# Top.net
KiCad netlist of a schematic drawn in Altium Designer
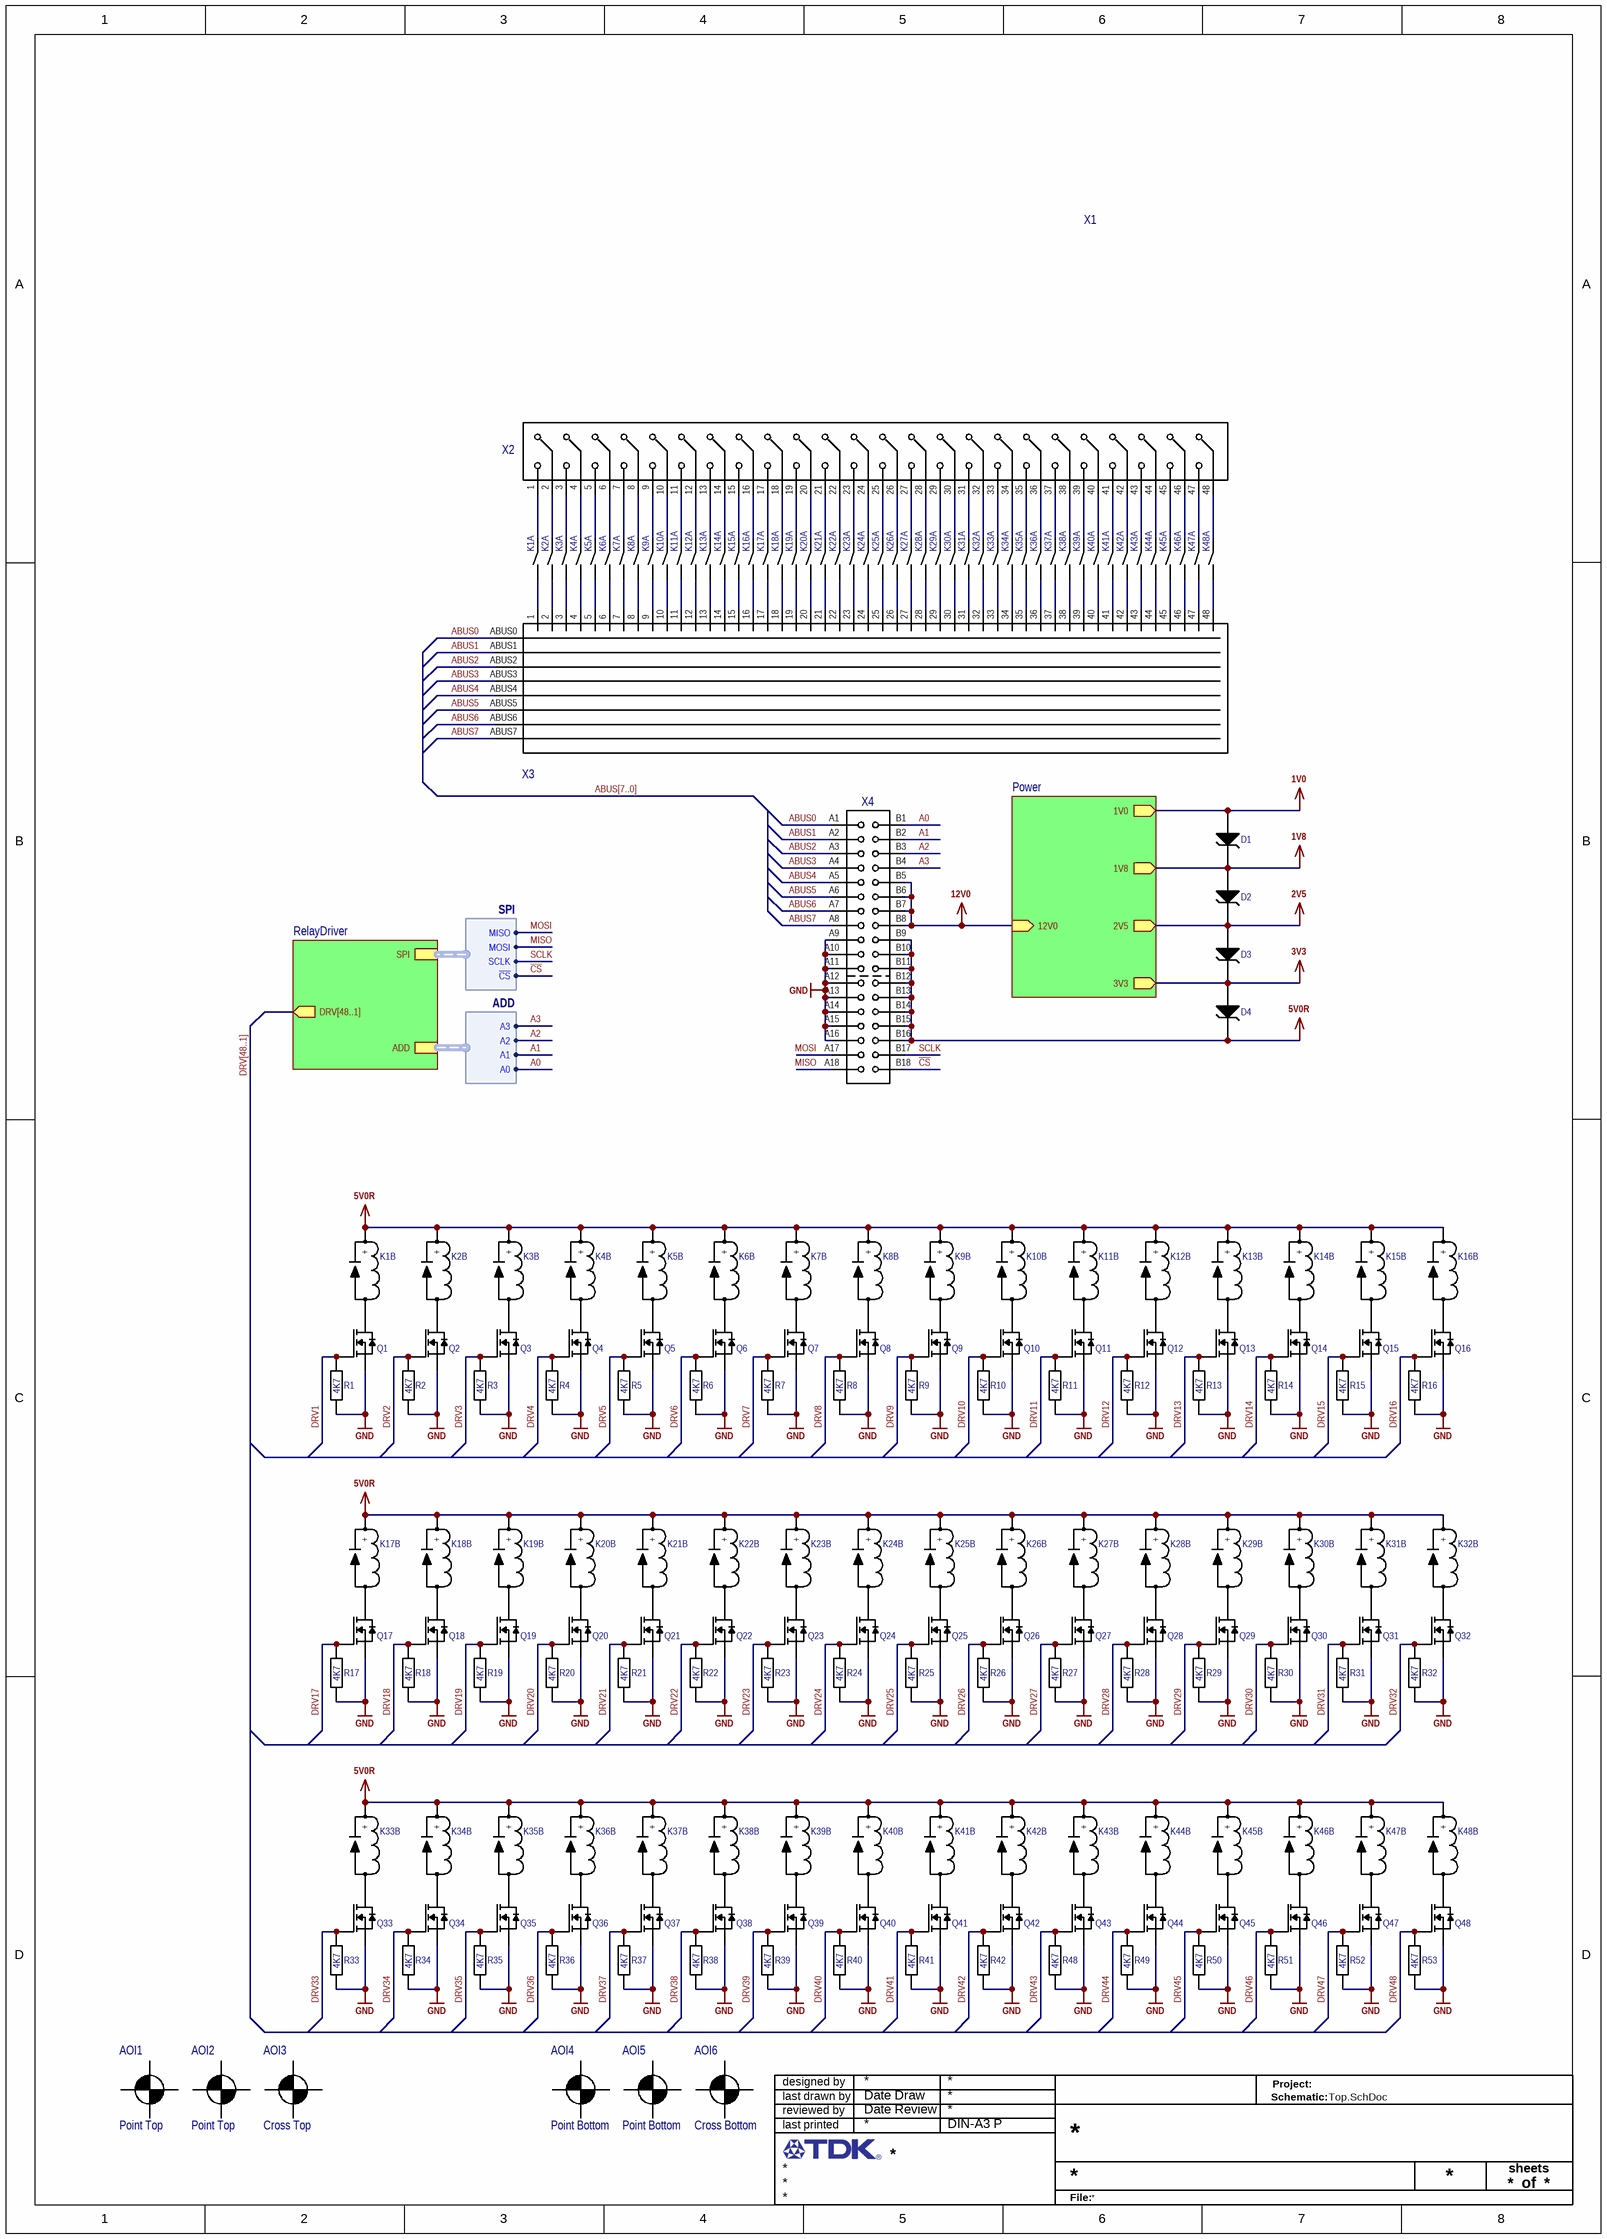
[diagram p0: Top.SchDoc]

(export (version "E")
  (design (tool "Eeschema 10.0.6"))
  (components
    (comp (ref "AOI1")
      (value "AOI")
      (footprint "Fiducial Point")
      (description "Assembly AOI")
      (fields (field (name "SHAPE") "Point Top") (field (name "13. CREATED DATE/NAME") "AUG2018/Hören"))
      (libsource (lib "chickenfood") (part "Fiducial"))
    )
    (comp (ref "AOI2")
      (value "AOI")
      (footprint "Fiducial Point")
      (description "Assembly AOI")
      (fields (field (name "SHAPE") "Point Top") (field (name "13. CREATED DATE/NAME") "AUG2018/Hören"))
      (libsource (lib "chickenfood") (part "Fiducial"))
    )
    (comp (ref "AOI3")
      (value "AOI")
      (footprint "Fiducial Cross")
      (description "Assembly AOI")
      (fields (field (name "SHAPE") "Cross Top") (field (name "13. CREATED DATE/NAME") "AUG2018/Hören"))
      (libsource (lib "chickenfood") (part "Fiducial"))
    )
    (comp (ref "AOI4")
      (value "AOI")
      (footprint "Fiducial Point")
      (description "Assembly AOI")
      (fields (field (name "SHAPE") "Point Bottom") (field (name "13. CREATED DATE/NAME") "AUG2018/Hören"))
      (libsource (lib "chickenfood") (part "Fiducial"))
    )
    (comp (ref "AOI5")
      (value "AOI")
      (footprint "Fiducial Point")
      (description "Assembly AOI")
      (fields (field (name "SHAPE") "Point Bottom") (field (name "13. CREATED DATE/NAME") "AUG2018/Hören"))
      (libsource (lib "chickenfood") (part "Fiducial"))
    )
    (comp (ref "AOI6")
      (value "AOI")
      (footprint "Fiducial Cross")
      (description "Assembly AOI")
      (fields (field (name "SHAPE") "Cross Bottom") (field (name "13. CREATED DATE/NAME") "AUG2018/Hören"))
      (libsource (lib "chickenfood") (part "Fiducial"))
    )
    (comp (ref "D1")
      (value "D")
      (footprint "SOD128")
      (description "DIODE SCHOTTKY 40V 5A SOD128")
      (fields
        (field (name "02. DISTRIBUTOR PART NUMBER") "1727-5842-6-ND")
        (field (name "07. MANUFACTURER  PART NUMBER") "PMEG4050EP,115")
        (field (name "13. CREATED DATE/NAME") "AUG2018/Hören")
      )
      (libsource (lib "chickenfood") (part "Dz"))
    )
    (comp (ref "D2")
      (value "D")
      (footprint "SOD128")
      (description "DIODE SCHOTTKY 40V 5A SOD128")
      (fields
        (field (name "02. DISTRIBUTOR PART NUMBER") "1727-5842-6-ND")
        (field (name "07. MANUFACTURER  PART NUMBER") "PMEG4050EP,115")
        (field (name "13. CREATED DATE/NAME") "AUG2018/Hören")
      )
      (libsource (lib "chickenfood") (part "Dz"))
    )
    (comp (ref "D3")
      (value "D")
      (footprint "SOD128")
      (description "DIODE SCHOTTKY 40V 5A SOD128")
      (fields
        (field (name "02. DISTRIBUTOR PART NUMBER") "1727-5842-6-ND")
        (field (name "07. MANUFACTURER  PART NUMBER") "PMEG4050EP,115")
        (field (name "13. CREATED DATE/NAME") "AUG2018/Hören")
      )
      (libsource (lib "chickenfood") (part "Dz"))
    )
    (comp (ref "D4")
      (value "D")
      (footprint "SOD128")
      (description "DIODE SCHOTTKY 40V 5A SOD128")
      (fields
        (field (name "02. DISTRIBUTOR PART NUMBER") "1727-5842-6-ND")
        (field (name "07. MANUFACTURER  PART NUMBER") "PMEG4050EP,115")
        (field (name "13. CREATED DATE/NAME") "AUG2018/Hören")
      )
      (libsource (lib "chickenfood") (part "Dz"))
    )
    (comp (ref "K1")
      (value "K")
      (footprint "118-1A")
      (description "5V Signal Relais, Normal Open")
      (fields
        (field (name "02. DISTRIBUTOR PART NUMBER") "118-1-A-5/2D")
        (field (name "13. CREATED DATE/NAME") "20.12.17 S. Kaiser")
      )
      (libsource (lib "") (part "118-1-A-5/2D_1"))
    )
    (comp (ref "K2")
      (value "K")
      (footprint "118-1A")
      (description "5V Signal Relais, Normal Open")
      (fields
        (field (name "02. DISTRIBUTOR PART NUMBER") "118-1-A-5/2D")
        (field (name "13. CREATED DATE/NAME") "20.12.17 S. Kaiser")
      )
      (libsource (lib "") (part "118-1-A-5/2D_1"))
    )
    (comp (ref "K3")
      (value "K")
      (footprint "118-1A")
      (description "5V Signal Relais, Normal Open")
      (fields
        (field (name "02. DISTRIBUTOR PART NUMBER") "118-1-A-5/2D")
        (field (name "13. CREATED DATE/NAME") "20.12.17 S. Kaiser")
      )
      (libsource (lib "") (part "118-1-A-5/2D_1"))
    )
    (comp (ref "K4")
      (value "K")
      (footprint "118-1A")
      (description "5V Signal Relais, Normal Open")
      (fields
        (field (name "02. DISTRIBUTOR PART NUMBER") "118-1-A-5/2D")
        (field (name "13. CREATED DATE/NAME") "20.12.17 S. Kaiser")
      )
      (libsource (lib "") (part "118-1-A-5/2D_1"))
    )
    (comp (ref "K5")
      (value "K")
      (footprint "118-1A")
      (description "5V Signal Relais, Normal Open")
      (fields
        (field (name "02. DISTRIBUTOR PART NUMBER") "118-1-A-5/2D")
        (field (name "13. CREATED DATE/NAME") "20.12.17 S. Kaiser")
      )
      (libsource (lib "chickenfood") (part "118-1-A-5/2D"))
    )
    (comp (ref "K6")
      (value "K")
      (footprint "118-1A")
      (description "5V Signal Relais, Normal Open")
      (fields
        (field (name "02. DISTRIBUTOR PART NUMBER") "118-1-A-5/2D")
        (field (name "13. CREATED DATE/NAME") "20.12.17 S. Kaiser")
      )
      (libsource (lib "") (part "118-1-A-5/2D_1"))
    )
    (comp (ref "K7")
      (value "K")
      (footprint "118-1A")
      (description "5V Signal Relais, Normal Open")
      (fields
        (field (name "02. DISTRIBUTOR PART NUMBER") "118-1-A-5/2D")
        (field (name "13. CREATED DATE/NAME") "20.12.17 S. Kaiser")
      )
      (libsource (lib "") (part "118-1-A-5/2D_1"))
    )
    (comp (ref "K8")
      (value "K")
      (footprint "118-1A")
      (description "5V Signal Relais, Normal Open")
      (fields
        (field (name "02. DISTRIBUTOR PART NUMBER") "118-1-A-5/2D")
        (field (name "13. CREATED DATE/NAME") "20.12.17 S. Kaiser")
      )
      (libsource (lib "chickenfood") (part "118-1-A-5/2D"))
    )
    (comp (ref "K9")
      (value "K")
      (footprint "118-1A")
      (description "5V Signal Relais, Normal Open")
      (fields
        (field (name "02. DISTRIBUTOR PART NUMBER") "118-1-A-5/2D")
        (field (name "13. CREATED DATE/NAME") "20.12.17 S. Kaiser")
      )
      (libsource (lib "") (part "118-1-A-5/2D_1"))
    )
    (comp (ref "K10")
      (value "K")
      (footprint "118-1A")
      (description "5V Signal Relais, Normal Open")
      (fields
        (field (name "02. DISTRIBUTOR PART NUMBER") "118-1-A-5/2D")
        (field (name "13. CREATED DATE/NAME") "20.12.17 S. Kaiser")
      )
      (libsource (lib "chickenfood") (part "118-1-A-5/2D"))
    )
    (comp (ref "K11")
      (value "K")
      (footprint "118-1A")
      (description "5V Signal Relais, Normal Open")
      (fields
        (field (name "02. DISTRIBUTOR PART NUMBER") "118-1-A-5/2D")
        (field (name "13. CREATED DATE/NAME") "20.12.17 S. Kaiser")
      )
      (libsource (lib "") (part "118-1-A-5/2D_1"))
    )
    (comp (ref "K12")
      (value "K")
      (footprint "118-1A")
      (description "5V Signal Relais, Normal Open")
      (fields
        (field (name "02. DISTRIBUTOR PART NUMBER") "118-1-A-5/2D")
        (field (name "13. CREATED DATE/NAME") "20.12.17 S. Kaiser")
      )
      (libsource (lib "chickenfood") (part "118-1-A-5/2D"))
    )
    (comp (ref "K13")
      (value "K")
      (footprint "118-1A")
      (description "5V Signal Relais, Normal Open")
      (fields
        (field (name "02. DISTRIBUTOR PART NUMBER") "118-1-A-5/2D")
        (field (name "13. CREATED DATE/NAME") "20.12.17 S. Kaiser")
      )
      (libsource (lib "chickenfood") (part "118-1-A-5/2D"))
    )
    (comp (ref "K14")
      (value "K")
      (footprint "118-1A")
      (description "5V Signal Relais, Normal Open")
      (fields
        (field (name "02. DISTRIBUTOR PART NUMBER") "118-1-A-5/2D")
        (field (name "13. CREATED DATE/NAME") "20.12.17 S. Kaiser")
      )
      (libsource (lib "chickenfood") (part "118-1-A-5/2D"))
    )
    (comp (ref "K15")
      (value "K")
      (footprint "118-1A")
      (description "5V Signal Relais, Normal Open")
      (fields
        (field (name "02. DISTRIBUTOR PART NUMBER") "118-1-A-5/2D")
        (field (name "13. CREATED DATE/NAME") "20.12.17 S. Kaiser")
      )
      (libsource (lib "") (part "118-1-A-5/2D_1"))
    )
    (comp (ref "K16")
      (value "K")
      (footprint "118-1A")
      (description "5V Signal Relais, Normal Open")
      (fields
        (field (name "02. DISTRIBUTOR PART NUMBER") "118-1-A-5/2D")
        (field (name "13. CREATED DATE/NAME") "20.12.17 S. Kaiser")
      )
      (libsource (lib "chickenfood") (part "118-1-A-5/2D"))
    )
    (comp (ref "K17")
      (value "K")
      (footprint "118-1A")
      (description "5V Signal Relais, Normal Open")
      (fields
        (field (name "02. DISTRIBUTOR PART NUMBER") "118-1-A-5/2D")
        (field (name "13. CREATED DATE/NAME") "20.12.17 S. Kaiser")
      )
      (libsource (lib "chickenfood") (part "118-1-A-5/2D"))
    )
    (comp (ref "K18")
      (value "K")
      (footprint "118-1A")
      (description "5V Signal Relais, Normal Open")
      (fields
        (field (name "02. DISTRIBUTOR PART NUMBER") "118-1-A-5/2D")
        (field (name "13. CREATED DATE/NAME") "20.12.17 S. Kaiser")
      )
      (libsource (lib "chickenfood") (part "118-1-A-5/2D"))
    )
    (comp (ref "K19")
      (value "K")
      (footprint "118-1A")
      (description "5V Signal Relais, Normal Open")
      (fields
        (field (name "02. DISTRIBUTOR PART NUMBER") "118-1-A-5/2D")
        (field (name "13. CREATED DATE/NAME") "20.12.17 S. Kaiser")
      )
      (libsource (lib "chickenfood") (part "118-1-A-5/2D"))
    )
    (comp (ref "K20")
      (value "K")
      (footprint "118-1A")
      (description "5V Signal Relais, Normal Open")
      (fields
        (field (name "02. DISTRIBUTOR PART NUMBER") "118-1-A-5/2D")
        (field (name "13. CREATED DATE/NAME") "20.12.17 S. Kaiser")
      )
      (libsource (lib "chickenfood") (part "118-1-A-5/2D"))
    )
    (comp (ref "K21")
      (value "K")
      (footprint "118-1A")
      (description "5V Signal Relais, Normal Open")
      (fields
        (field (name "02. DISTRIBUTOR PART NUMBER") "118-1-A-5/2D")
        (field (name "13. CREATED DATE/NAME") "20.12.17 S. Kaiser")
      )
      (libsource (lib "") (part "118-1-A-5/2D_1"))
    )
    (comp (ref "K22")
      (value "K")
      (footprint "118-1A")
      (description "5V Signal Relais, Normal Open")
      (fields
        (field (name "02. DISTRIBUTOR PART NUMBER") "118-1-A-5/2D")
        (field (name "13. CREATED DATE/NAME") "20.12.17 S. Kaiser")
      )
      (libsource (lib "chickenfood") (part "118-1-A-5/2D"))
    )
    (comp (ref "K23")
      (value "K")
      (footprint "118-1A")
      (description "5V Signal Relais, Normal Open")
      (fields
        (field (name "02. DISTRIBUTOR PART NUMBER") "118-1-A-5/2D")
        (field (name "13. CREATED DATE/NAME") "20.12.17 S. Kaiser")
      )
      (libsource (lib "chickenfood") (part "118-1-A-5/2D"))
    )
    (comp (ref "K24")
      (value "K")
      (footprint "118-1A")
      (description "5V Signal Relais, Normal Open")
      (fields
        (field (name "02. DISTRIBUTOR PART NUMBER") "118-1-A-5/2D")
        (field (name "13. CREATED DATE/NAME") "20.12.17 S. Kaiser")
      )
      (libsource (lib "") (part "118-1-A-5/2D_1"))
    )
    (comp (ref "K25")
      (value "K")
      (footprint "118-1A")
      (description "5V Signal Relais, Normal Open")
      (fields
        (field (name "02. DISTRIBUTOR PART NUMBER") "118-1-A-5/2D")
        (field (name "13. CREATED DATE/NAME") "20.12.17 S. Kaiser")
      )
      (libsource (lib "chickenfood") (part "118-1-A-5/2D"))
    )
    (comp (ref "K26")
      (value "K")
      (footprint "118-1A")
      (description "5V Signal Relais, Normal Open")
      (fields
        (field (name "02. DISTRIBUTOR PART NUMBER") "118-1-A-5/2D")
        (field (name "13. CREATED DATE/NAME") "20.12.17 S. Kaiser")
      )
      (libsource (lib "") (part "118-1-A-5/2D_1"))
    )
    (comp (ref "K27")
      (value "K")
      (footprint "118-1A")
      (description "5V Signal Relais, Normal Open")
      (fields
        (field (name "02. DISTRIBUTOR PART NUMBER") "118-1-A-5/2D")
        (field (name "13. CREATED DATE/NAME") "20.12.17 S. Kaiser")
      )
      (libsource (lib "") (part "118-1-A-5/2D_1"))
    )
    (comp (ref "K28")
      (value "K")
      (footprint "118-1A")
      (description "5V Signal Relais, Normal Open")
      (fields
        (field (name "02. DISTRIBUTOR PART NUMBER") "118-1-A-5/2D")
        (field (name "13. CREATED DATE/NAME") "20.12.17 S. Kaiser")
      )
      (libsource (lib "") (part "118-1-A-5/2D_1"))
    )
    (comp (ref "K29")
      (value "K")
      (footprint "118-1A")
      (description "5V Signal Relais, Normal Open")
      (fields
        (field (name "02. DISTRIBUTOR PART NUMBER") "118-1-A-5/2D")
        (field (name "13. CREATED DATE/NAME") "20.12.17 S. Kaiser")
      )
      (libsource (lib "") (part "118-1-A-5/2D_1"))
    )
    (comp (ref "K30")
      (value "K")
      (footprint "118-1A")
      (description "5V Signal Relais, Normal Open")
      (fields
        (field (name "02. DISTRIBUTOR PART NUMBER") "118-1-A-5/2D")
        (field (name "13. CREATED DATE/NAME") "20.12.17 S. Kaiser")
      )
      (libsource (lib "") (part "118-1-A-5/2D_1"))
    )
    (comp (ref "K31")
      (value "K")
      (footprint "118-1A")
      (description "5V Signal Relais, Normal Open")
      (fields
        (field (name "02. DISTRIBUTOR PART NUMBER") "118-1-A-5/2D")
        (field (name "13. CREATED DATE/NAME") "20.12.17 S. Kaiser")
      )
      (libsource (lib "") (part "118-1-A-5/2D_1"))
    )
    (comp (ref "K32")
      (value "K")
      (footprint "118-1A")
      (description "5V Signal Relais, Normal Open")
      (fields
        (field (name "02. DISTRIBUTOR PART NUMBER") "118-1-A-5/2D")
        (field (name "13. CREATED DATE/NAME") "20.12.17 S. Kaiser")
      )
      (libsource (lib "chickenfood") (part "118-1-A-5/2D"))
    )
    (comp (ref "K33")
      (value "K")
      (footprint "118-1A")
      (description "5V Signal Relais, Normal Open")
      (fields
        (field (name "02. DISTRIBUTOR PART NUMBER") "118-1-A-5/2D")
        (field (name "13. CREATED DATE/NAME") "20.12.17 S. Kaiser")
      )
      (libsource (lib "") (part "118-1-A-5/2D_1"))
    )
    (comp (ref "K34")
      (value "K")
      (footprint "118-1A")
      (description "5V Signal Relais, Normal Open")
      (fields
        (field (name "02. DISTRIBUTOR PART NUMBER") "118-1-A-5/2D")
        (field (name "13. CREATED DATE/NAME") "20.12.17 S. Kaiser")
      )
      (libsource (lib "chickenfood") (part "118-1-A-5/2D"))
    )
    (comp (ref "K35")
      (value "K")
      (footprint "118-1A")
      (description "5V Signal Relais, Normal Open")
      (fields
        (field (name "02. DISTRIBUTOR PART NUMBER") "118-1-A-5/2D")
        (field (name "13. CREATED DATE/NAME") "20.12.17 S. Kaiser")
      )
      (libsource (lib "chickenfood") (part "118-1-A-5/2D"))
    )
    (comp (ref "K36")
      (value "K")
      (footprint "118-1A")
      (description "5V Signal Relais, Normal Open")
      (fields
        (field (name "02. DISTRIBUTOR PART NUMBER") "118-1-A-5/2D")
        (field (name "13. CREATED DATE/NAME") "20.12.17 S. Kaiser")
      )
      (libsource (lib "") (part "118-1-A-5/2D_1"))
    )
    (comp (ref "K37")
      (value "K")
      (footprint "118-1A")
      (description "5V Signal Relais, Normal Open")
      (fields
        (field (name "02. DISTRIBUTOR PART NUMBER") "118-1-A-5/2D")
        (field (name "13. CREATED DATE/NAME") "20.12.17 S. Kaiser")
      )
      (libsource (lib "") (part "118-1-A-5/2D_1"))
    )
    (comp (ref "K38")
      (value "K")
      (footprint "118-1A")
      (description "5V Signal Relais, Normal Open")
      (fields
        (field (name "02. DISTRIBUTOR PART NUMBER") "118-1-A-5/2D")
        (field (name "13. CREATED DATE/NAME") "20.12.17 S. Kaiser")
      )
      (libsource (lib "chickenfood") (part "118-1-A-5/2D"))
    )
    (comp (ref "K39")
      (value "K")
      (footprint "118-1A")
      (description "5V Signal Relais, Normal Open")
      (fields
        (field (name "02. DISTRIBUTOR PART NUMBER") "118-1-A-5/2D")
        (field (name "13. CREATED DATE/NAME") "20.12.17 S. Kaiser")
      )
      (libsource (lib "") (part "118-1-A-5/2D_1"))
    )
    (comp (ref "K40")
      (value "K")
      (footprint "118-1A")
      (description "5V Signal Relais, Normal Open")
      (fields
        (field (name "02. DISTRIBUTOR PART NUMBER") "118-1-A-5/2D")
        (field (name "13. CREATED DATE/NAME") "20.12.17 S. Kaiser")
      )
      (libsource (lib "") (part "118-1-A-5/2D_1"))
    )
    (comp (ref "K41")
      (value "K")
      (footprint "118-1A")
      (description "5V Signal Relais, Normal Open")
      (fields
        (field (name "02. DISTRIBUTOR PART NUMBER") "118-1-A-5/2D")
        (field (name "13. CREATED DATE/NAME") "20.12.17 S. Kaiser")
      )
      (libsource (lib "chickenfood") (part "118-1-A-5/2D"))
    )
    (comp (ref "K42")
      (value "K")
      (footprint "118-1A")
      (description "5V Signal Relais, Normal Open")
      (fields
        (field (name "02. DISTRIBUTOR PART NUMBER") "118-1-A-5/2D")
        (field (name "13. CREATED DATE/NAME") "20.12.17 S. Kaiser")
      )
      (libsource (lib "") (part "118-1-A-5/2D_1"))
    )
    (comp (ref "K43")
      (value "K")
      (footprint "118-1A")
      (description "5V Signal Relais, Normal Open")
      (fields
        (field (name "02. DISTRIBUTOR PART NUMBER") "118-1-A-5/2D")
        (field (name "13. CREATED DATE/NAME") "20.12.17 S. Kaiser")
      )
      (libsource (lib "chickenfood") (part "118-1-A-5/2D"))
    )
    (comp (ref "K44")
      (value "K")
      (footprint "118-1A")
      (description "5V Signal Relais, Normal Open")
      (fields
        (field (name "02. DISTRIBUTOR PART NUMBER") "118-1-A-5/2D")
        (field (name "13. CREATED DATE/NAME") "20.12.17 S. Kaiser")
      )
      (libsource (lib "chickenfood") (part "118-1-A-5/2D"))
    )
    (comp (ref "K45")
      (value "K")
      (footprint "118-1A")
      (description "5V Signal Relais, Normal Open")
      (fields
        (field (name "02. DISTRIBUTOR PART NUMBER") "118-1-A-5/2D")
        (field (name "13. CREATED DATE/NAME") "20.12.17 S. Kaiser")
      )
      (libsource (lib "") (part "118-1-A-5/2D_1"))
    )
    (comp (ref "K46")
      (value "K")
      (footprint "118-1A")
      (description "5V Signal Relais, Normal Open")
      (fields
        (field (name "02. DISTRIBUTOR PART NUMBER") "118-1-A-5/2D")
        (field (name "13. CREATED DATE/NAME") "20.12.17 S. Kaiser")
      )
      (libsource (lib "") (part "118-1-A-5/2D_1"))
    )
    (comp (ref "K47")
      (value "K")
      (footprint "118-1A")
      (description "5V Signal Relais, Normal Open")
      (fields
        (field (name "02. DISTRIBUTOR PART NUMBER") "118-1-A-5/2D")
        (field (name "13. CREATED DATE/NAME") "20.12.17 S. Kaiser")
      )
      (libsource (lib "chickenfood") (part "118-1-A-5/2D"))
    )
    (comp (ref "K48")
      (value "K")
      (footprint "118-1A")
      (description "5V Signal Relais, Normal Open")
      (fields
        (field (name "02. DISTRIBUTOR PART NUMBER") "118-1-A-5/2D")
        (field (name "13. CREATED DATE/NAME") "20.12.17 S. Kaiser")
      )
      (libsource (lib "") (part "118-1-A-5/2D_1"))
    )
    (comp (ref "Q1")
      (value "Q")
      (footprint "SOT23-3")
      (description "MOSFET N-CH 25V 680MA SOT-23")
      (fields
        (field (name "02. DISTRIBUTOR PART NUMBER") "FDV303NDKR-ND")
        (field (name "07. MANUFACTURER  PART NUMBER") "FDV303N")
        (field (name "13. CREATED DATE/NAME") "AUG 2018 / Hören")
      )
      (libsource (lib "SCT8-Board1") (part "FDV303N"))
    )
    (comp (ref "Q2")
      (value "Q")
      (footprint "SOT23-3")
      (description "MOSFET N-CH 25V 680MA SOT-23")
      (fields
        (field (name "02. DISTRIBUTOR PART NUMBER") "FDV303NDKR-ND")
        (field (name "07. MANUFACTURER  PART NUMBER") "FDV303N")
        (field (name "13. CREATED DATE/NAME") "AUG 2018 / Hören")
      )
      (libsource (lib "SCT8-Board1") (part "FDV303N"))
    )
    (comp (ref "Q3")
      (value "Q")
      (footprint "SOT23-3")
      (description "MOSFET N-CH 25V 680MA SOT-23")
      (fields
        (field (name "02. DISTRIBUTOR PART NUMBER") "FDV303NDKR-ND")
        (field (name "07. MANUFACTURER  PART NUMBER") "FDV303N")
        (field (name "13. CREATED DATE/NAME") "AUG 2018 / Hören")
      )
      (libsource (lib "SCT8-Board1") (part "FDV303N"))
    )
    (comp (ref "Q4")
      (value "Q")
      (footprint "SOT23-3")
      (description "MOSFET N-CH 25V 680MA SOT-23")
      (fields
        (field (name "02. DISTRIBUTOR PART NUMBER") "FDV303NDKR-ND")
        (field (name "07. MANUFACTURER  PART NUMBER") "FDV303N")
        (field (name "13. CREATED DATE/NAME") "AUG 2018 / Hören")
      )
      (libsource (lib "SCT8-Board1") (part "FDV303N"))
    )
    (comp (ref "Q5")
      (value "Q")
      (footprint "SOT23-3")
      (description "MOSFET N-CH 25V 680MA SOT-23")
      (fields
        (field (name "02. DISTRIBUTOR PART NUMBER") "FDV303NDKR-ND")
        (field (name "07. MANUFACTURER  PART NUMBER") "FDV303N")
        (field (name "13. CREATED DATE/NAME") "AUG 2018 / Hören")
      )
      (libsource (lib "SCT8-Board1") (part "FDV303N"))
    )
    (comp (ref "Q6")
      (value "Q")
      (footprint "SOT23-3")
      (description "MOSFET N-CH 25V 680MA SOT-23")
      (fields
        (field (name "02. DISTRIBUTOR PART NUMBER") "FDV303NDKR-ND")
        (field (name "07. MANUFACTURER  PART NUMBER") "FDV303N")
        (field (name "13. CREATED DATE/NAME") "AUG 2018 / Hören")
      )
      (libsource (lib "SCT8-Board1") (part "FDV303N"))
    )
    (comp (ref "Q7")
      (value "Q")
      (footprint "SOT23-3")
      (description "MOSFET N-CH 25V 680MA SOT-23")
      (fields
        (field (name "02. DISTRIBUTOR PART NUMBER") "FDV303NDKR-ND")
        (field (name "07. MANUFACTURER  PART NUMBER") "FDV303N")
        (field (name "13. CREATED DATE/NAME") "AUG 2018 / Hören")
      )
      (libsource (lib "SCT8-Board1") (part "FDV303N"))
    )
    (comp (ref "Q8")
      (value "Q")
      (footprint "SOT23-3")
      (description "MOSFET N-CH 25V 680MA SOT-23")
      (fields
        (field (name "02. DISTRIBUTOR PART NUMBER") "FDV303NDKR-ND")
        (field (name "07. MANUFACTURER  PART NUMBER") "FDV303N")
        (field (name "13. CREATED DATE/NAME") "AUG 2018 / Hören")
      )
      (libsource (lib "SCT8-Board1") (part "FDV303N"))
    )
    (comp (ref "Q9")
      (value "Q")
      (footprint "SOT23-3")
      (description "MOSFET N-CH 25V 680MA SOT-23")
      (fields
        (field (name "02. DISTRIBUTOR PART NUMBER") "FDV303NDKR-ND")
        (field (name "07. MANUFACTURER  PART NUMBER") "FDV303N")
        (field (name "13. CREATED DATE/NAME") "AUG 2018 / Hören")
      )
      (libsource (lib "SCT8-Board1") (part "FDV303N"))
    )
    (comp (ref "Q10")
      (value "Q")
      (footprint "SOT23-3")
      (description "MOSFET N-CH 25V 680MA SOT-23")
      (fields
        (field (name "02. DISTRIBUTOR PART NUMBER") "FDV303NDKR-ND")
        (field (name "07. MANUFACTURER  PART NUMBER") "FDV303N")
        (field (name "13. CREATED DATE/NAME") "AUG 2018 / Hören")
      )
      (libsource (lib "SCT8-Board1") (part "FDV303N"))
    )
    (comp (ref "Q11")
      (value "Q")
      (footprint "SOT23-3")
      (description "MOSFET N-CH 25V 680MA SOT-23")
      (fields
        (field (name "02. DISTRIBUTOR PART NUMBER") "FDV303NDKR-ND")
        (field (name "07. MANUFACTURER  PART NUMBER") "FDV303N")
        (field (name "13. CREATED DATE/NAME") "AUG 2018 / Hören")
      )
      (libsource (lib "SCT8-Board1") (part "FDV303N"))
    )
    (comp (ref "Q12")
      (value "Q")
      (footprint "SOT23-3")
      (description "MOSFET N-CH 25V 680MA SOT-23")
      (fields
        (field (name "02. DISTRIBUTOR PART NUMBER") "FDV303NDKR-ND")
        (field (name "07. MANUFACTURER  PART NUMBER") "FDV303N")
        (field (name "13. CREATED DATE/NAME") "AUG 2018 / Hören")
      )
      (libsource (lib "SCT8-Board1") (part "FDV303N"))
    )
    (comp (ref "Q13")
      (value "Q")
      (footprint "SOT23-3")
      (description "MOSFET N-CH 25V 680MA SOT-23")
      (fields
        (field (name "02. DISTRIBUTOR PART NUMBER") "FDV303NDKR-ND")
        (field (name "07. MANUFACTURER  PART NUMBER") "FDV303N")
        (field (name "13. CREATED DATE/NAME") "AUG 2018 / Hören")
      )
      (libsource (lib "SCT8-Board1") (part "FDV303N"))
    )
    (comp (ref "Q14")
      (value "Q")
      (footprint "SOT23-3")
      (description "MOSFET N-CH 25V 680MA SOT-23")
      (fields
        (field (name "02. DISTRIBUTOR PART NUMBER") "FDV303NDKR-ND")
        (field (name "07. MANUFACTURER  PART NUMBER") "FDV303N")
        (field (name "13. CREATED DATE/NAME") "AUG 2018 / Hören")
      )
      (libsource (lib "SCT8-Board1") (part "FDV303N"))
    )
    (comp (ref "Q15")
      (value "Q")
      (footprint "SOT23-3")
      (description "MOSFET N-CH 25V 680MA SOT-23")
      (fields
        (field (name "02. DISTRIBUTOR PART NUMBER") "FDV303NDKR-ND")
        (field (name "07. MANUFACTURER  PART NUMBER") "FDV303N")
        (field (name "13. CREATED DATE/NAME") "AUG 2018 / Hören")
      )
      (libsource (lib "SCT8-Board1") (part "FDV303N"))
    )
    (comp (ref "Q16")
      (value "Q")
      (footprint "SOT23-3")
      (description "MOSFET N-CH 25V 680MA SOT-23")
      (fields
        (field (name "02. DISTRIBUTOR PART NUMBER") "FDV303NDKR-ND")
        (field (name "07. MANUFACTURER  PART NUMBER") "FDV303N")
        (field (name "13. CREATED DATE/NAME") "AUG 2018 / Hören")
      )
      (libsource (lib "SCT8-Board1") (part "FDV303N"))
    )
    (comp (ref "Q17")
      (value "Q")
      (footprint "SOT23-3")
      (description "MOSFET N-CH 25V 680MA SOT-23")
      (fields
        (field (name "02. DISTRIBUTOR PART NUMBER") "FDV303NDKR-ND")
        (field (name "07. MANUFACTURER  PART NUMBER") "FDV303N")
        (field (name "13. CREATED DATE/NAME") "AUG 2018 / Hören")
      )
      (libsource (lib "SCT8-Board1") (part "FDV303N"))
    )
    (comp (ref "Q18")
      (value "Q")
      (footprint "SOT23-3")
      (description "MOSFET N-CH 25V 680MA SOT-23")
      (fields
        (field (name "02. DISTRIBUTOR PART NUMBER") "FDV303NDKR-ND")
        (field (name "07. MANUFACTURER  PART NUMBER") "FDV303N")
        (field (name "13. CREATED DATE/NAME") "AUG 2018 / Hören")
      )
      (libsource (lib "SCT8-Board1") (part "FDV303N"))
    )
    (comp (ref "Q19")
      (value "Q")
      (footprint "SOT23-3")
      (description "MOSFET N-CH 25V 680MA SOT-23")
      (fields
        (field (name "02. DISTRIBUTOR PART NUMBER") "FDV303NDKR-ND")
        (field (name "07. MANUFACTURER  PART NUMBER") "FDV303N")
        (field (name "13. CREATED DATE/NAME") "AUG 2018 / Hören")
      )
      (libsource (lib "SCT8-Board1") (part "FDV303N"))
    )
    (comp (ref "Q20")
      (value "Q")
      (footprint "SOT23-3")
      (description "MOSFET N-CH 25V 680MA SOT-23")
      (fields
        (field (name "02. DISTRIBUTOR PART NUMBER") "FDV303NDKR-ND")
        (field (name "07. MANUFACTURER  PART NUMBER") "FDV303N")
        (field (name "13. CREATED DATE/NAME") "AUG 2018 / Hören")
      )
      (libsource (lib "SCT8-Board1") (part "FDV303N"))
    )
    (comp (ref "Q21")
      (value "Q")
      (footprint "SOT23-3")
      (description "MOSFET N-CH 25V 680MA SOT-23")
      (fields
        (field (name "02. DISTRIBUTOR PART NUMBER") "FDV303NDKR-ND")
        (field (name "07. MANUFACTURER  PART NUMBER") "FDV303N")
        (field (name "13. CREATED DATE/NAME") "AUG 2018 / Hören")
      )
      (libsource (lib "SCT8-Board1") (part "FDV303N"))
    )
    (comp (ref "Q22")
      (value "Q")
      (footprint "SOT23-3")
      (description "MOSFET N-CH 25V 680MA SOT-23")
      (fields
        (field (name "02. DISTRIBUTOR PART NUMBER") "FDV303NDKR-ND")
        (field (name "07. MANUFACTURER  PART NUMBER") "FDV303N")
        (field (name "13. CREATED DATE/NAME") "AUG 2018 / Hören")
      )
      (libsource (lib "SCT8-Board1") (part "FDV303N"))
    )
    (comp (ref "Q23")
      (value "Q")
      (footprint "SOT23-3")
      (description "MOSFET N-CH 25V 680MA SOT-23")
      (fields
        (field (name "02. DISTRIBUTOR PART NUMBER") "FDV303NDKR-ND")
        (field (name "07. MANUFACTURER  PART NUMBER") "FDV303N")
        (field (name "13. CREATED DATE/NAME") "AUG 2018 / Hören")
      )
      (libsource (lib "SCT8-Board1") (part "FDV303N"))
    )
    (comp (ref "Q24")
      (value "Q")
      (footprint "SOT23-3")
      (description "MOSFET N-CH 25V 680MA SOT-23")
      (fields
        (field (name "02. DISTRIBUTOR PART NUMBER") "FDV303NDKR-ND")
        (field (name "07. MANUFACTURER  PART NUMBER") "FDV303N")
        (field (name "13. CREATED DATE/NAME") "AUG 2018 / Hören")
      )
      (libsource (lib "SCT8-Board1") (part "FDV303N"))
    )
    (comp (ref "Q25")
      (value "Q")
      (footprint "SOT23-3")
      (description "MOSFET N-CH 25V 680MA SOT-23")
      (fields
        (field (name "02. DISTRIBUTOR PART NUMBER") "FDV303NDKR-ND")
        (field (name "07. MANUFACTURER  PART NUMBER") "FDV303N")
        (field (name "13. CREATED DATE/NAME") "AUG 2018 / Hören")
      )
      (libsource (lib "SCT8-Board1") (part "FDV303N"))
    )
    (comp (ref "Q26")
      (value "Q")
      (footprint "SOT23-3")
      (description "MOSFET N-CH 25V 680MA SOT-23")
      (fields
        (field (name "02. DISTRIBUTOR PART NUMBER") "FDV303NDKR-ND")
        (field (name "07. MANUFACTURER  PART NUMBER") "FDV303N")
        (field (name "13. CREATED DATE/NAME") "AUG 2018 / Hören")
      )
      (libsource (lib "SCT8-Board1") (part "FDV303N"))
    )
    (comp (ref "Q27")
      (value "Q")
      (footprint "SOT23-3")
      (description "MOSFET N-CH 25V 680MA SOT-23")
      (fields
        (field (name "02. DISTRIBUTOR PART NUMBER") "FDV303NDKR-ND")
        (field (name "07. MANUFACTURER  PART NUMBER") "FDV303N")
        (field (name "13. CREATED DATE/NAME") "AUG 2018 / Hören")
      )
      (libsource (lib "SCT8-Board1") (part "FDV303N"))
    )
    (comp (ref "Q28")
      (value "Q")
      (footprint "SOT23-3")
      (description "MOSFET N-CH 25V 680MA SOT-23")
      (fields
        (field (name "02. DISTRIBUTOR PART NUMBER") "FDV303NDKR-ND")
        (field (name "07. MANUFACTURER  PART NUMBER") "FDV303N")
        (field (name "13. CREATED DATE/NAME") "AUG 2018 / Hören")
      )
      (libsource (lib "SCT8-Board1") (part "FDV303N"))
    )
    (comp (ref "Q29")
      (value "Q")
      (footprint "SOT23-3")
      (description "MOSFET N-CH 25V 680MA SOT-23")
      (fields
        (field (name "02. DISTRIBUTOR PART NUMBER") "FDV303NDKR-ND")
        (field (name "07. MANUFACTURER  PART NUMBER") "FDV303N")
        (field (name "13. CREATED DATE/NAME") "AUG 2018 / Hören")
      )
      (libsource (lib "SCT8-Board1") (part "FDV303N"))
    )
    (comp (ref "Q30")
      (value "Q")
      (footprint "SOT23-3")
      (description "MOSFET N-CH 25V 680MA SOT-23")
      (fields
        (field (name "02. DISTRIBUTOR PART NUMBER") "FDV303NDKR-ND")
        (field (name "07. MANUFACTURER  PART NUMBER") "FDV303N")
        (field (name "13. CREATED DATE/NAME") "AUG 2018 / Hören")
      )
      (libsource (lib "SCT8-Board1") (part "FDV303N"))
    )
    (comp (ref "Q31")
      (value "Q")
      (footprint "SOT23-3")
      (description "MOSFET N-CH 25V 680MA SOT-23")
      (fields
        (field (name "02. DISTRIBUTOR PART NUMBER") "FDV303NDKR-ND")
        (field (name "07. MANUFACTURER  PART NUMBER") "FDV303N")
        (field (name "13. CREATED DATE/NAME") "AUG 2018 / Hören")
      )
      (libsource (lib "SCT8-Board1") (part "FDV303N"))
    )
    (comp (ref "Q32")
      (value "Q")
      (footprint "SOT23-3")
      (description "MOSFET N-CH 25V 680MA SOT-23")
      (fields
        (field (name "02. DISTRIBUTOR PART NUMBER") "FDV303NDKR-ND")
        (field (name "07. MANUFACTURER  PART NUMBER") "FDV303N")
        (field (name "13. CREATED DATE/NAME") "AUG 2018 / Hören")
      )
      (libsource (lib "SCT8-Board1") (part "FDV303N"))
    )
    (comp (ref "Q33")
      (value "Q")
      (footprint "SOT23-3")
      (description "MOSFET N-CH 25V 680MA SOT-23")
      (fields
        (field (name "02. DISTRIBUTOR PART NUMBER") "FDV303NDKR-ND")
        (field (name "07. MANUFACTURER  PART NUMBER") "FDV303N")
        (field (name "13. CREATED DATE/NAME") "AUG 2018 / Hören")
      )
      (libsource (lib "SCT8-Board1") (part "FDV303N"))
    )
    (comp (ref "Q34")
      (value "Q")
      (footprint "SOT23-3")
      (description "MOSFET N-CH 25V 680MA SOT-23")
      (fields
        (field (name "02. DISTRIBUTOR PART NUMBER") "FDV303NDKR-ND")
        (field (name "07. MANUFACTURER  PART NUMBER") "FDV303N")
        (field (name "13. CREATED DATE/NAME") "AUG 2018 / Hören")
      )
      (libsource (lib "SCT8-Board1") (part "FDV303N"))
    )
    (comp (ref "Q35")
      (value "Q")
      (footprint "SOT23-3")
      (description "MOSFET N-CH 25V 680MA SOT-23")
      (fields
        (field (name "02. DISTRIBUTOR PART NUMBER") "FDV303NDKR-ND")
        (field (name "07. MANUFACTURER  PART NUMBER") "FDV303N")
        (field (name "13. CREATED DATE/NAME") "AUG 2018 / Hören")
      )
      (libsource (lib "SCT8-Board1") (part "FDV303N"))
    )
    (comp (ref "Q36")
      (value "Q")
      (footprint "SOT23-3")
      (description "MOSFET N-CH 25V 680MA SOT-23")
      (fields
        (field (name "02. DISTRIBUTOR PART NUMBER") "FDV303NDKR-ND")
        (field (name "07. MANUFACTURER  PART NUMBER") "FDV303N")
        (field (name "13. CREATED DATE/NAME") "AUG 2018 / Hören")
      )
      (libsource (lib "SCT8-Board1") (part "FDV303N"))
    )
    (comp (ref "Q37")
      (value "Q")
      (footprint "SOT23-3")
      (description "MOSFET N-CH 25V 680MA SOT-23")
      (fields
        (field (name "02. DISTRIBUTOR PART NUMBER") "FDV303NDKR-ND")
        (field (name "07. MANUFACTURER  PART NUMBER") "FDV303N")
        (field (name "13. CREATED DATE/NAME") "AUG 2018 / Hören")
      )
      (libsource (lib "SCT8-Board1") (part "FDV303N"))
    )
    (comp (ref "Q38")
      (value "Q")
      (footprint "SOT23-3")
      (description "MOSFET N-CH 25V 680MA SOT-23")
      (fields
        (field (name "02. DISTRIBUTOR PART NUMBER") "FDV303NDKR-ND")
        (field (name "07. MANUFACTURER  PART NUMBER") "FDV303N")
        (field (name "13. CREATED DATE/NAME") "AUG 2018 / Hören")
      )
      (libsource (lib "SCT8-Board1") (part "FDV303N"))
    )
    (comp (ref "Q39")
      (value "Q")
      (footprint "SOT23-3")
      (description "MOSFET N-CH 25V 680MA SOT-23")
      (fields
        (field (name "02. DISTRIBUTOR PART NUMBER") "FDV303NDKR-ND")
        (field (name "07. MANUFACTURER  PART NUMBER") "FDV303N")
        (field (name "13. CREATED DATE/NAME") "AUG 2018 / Hören")
      )
      (libsource (lib "SCT8-Board1") (part "FDV303N"))
    )
    (comp (ref "Q40")
      (value "Q")
      (footprint "SOT23-3")
      (description "MOSFET N-CH 25V 680MA SOT-23")
      (fields
        (field (name "02. DISTRIBUTOR PART NUMBER") "FDV303NDKR-ND")
        (field (name "07. MANUFACTURER  PART NUMBER") "FDV303N")
        (field (name "13. CREATED DATE/NAME") "AUG 2018 / Hören")
      )
      (libsource (lib "SCT8-Board1") (part "FDV303N"))
    )
    (comp (ref "Q41")
      (value "Q")
      (footprint "SOT23-3")
      (description "MOSFET N-CH 25V 680MA SOT-23")
      (fields
        (field (name "02. DISTRIBUTOR PART NUMBER") "FDV303NDKR-ND")
        (field (name "07. MANUFACTURER  PART NUMBER") "FDV303N")
        (field (name "13. CREATED DATE/NAME") "AUG 2018 / Hören")
      )
      (libsource (lib "SCT8-Board1") (part "FDV303N"))
    )
    (comp (ref "Q42")
      (value "Q")
      (footprint "SOT23-3")
      (description "MOSFET N-CH 25V 680MA SOT-23")
      (fields
        (field (name "02. DISTRIBUTOR PART NUMBER") "FDV303NDKR-ND")
        (field (name "07. MANUFACTURER  PART NUMBER") "FDV303N")
        (field (name "13. CREATED DATE/NAME") "AUG 2018 / Hören")
      )
      (libsource (lib "SCT8-Board1") (part "FDV303N"))
    )
    (comp (ref "Q43")
      (value "Q")
      (footprint "SOT23-3")
      (description "MOSFET N-CH 25V 680MA SOT-23")
      (fields
        (field (name "02. DISTRIBUTOR PART NUMBER") "FDV303NDKR-ND")
        (field (name "07. MANUFACTURER  PART NUMBER") "FDV303N")
        (field (name "13. CREATED DATE/NAME") "AUG 2018 / Hören")
      )
      (libsource (lib "SCT8-Board1") (part "FDV303N"))
    )
    (comp (ref "Q44")
      (value "Q")
      (footprint "SOT23-3")
      (description "MOSFET N-CH 25V 680MA SOT-23")
      (fields
        (field (name "02. DISTRIBUTOR PART NUMBER") "FDV303NDKR-ND")
        (field (name "07. MANUFACTURER  PART NUMBER") "FDV303N")
        (field (name "13. CREATED DATE/NAME") "AUG 2018 / Hören")
      )
      (libsource (lib "SCT8-Board1") (part "FDV303N"))
    )
    (comp (ref "Q45")
      (value "Q")
      (footprint "SOT23-3")
      (description "MOSFET N-CH 25V 680MA SOT-23")
      (fields
        (field (name "02. DISTRIBUTOR PART NUMBER") "FDV303NDKR-ND")
        (field (name "07. MANUFACTURER  PART NUMBER") "FDV303N")
        (field (name "13. CREATED DATE/NAME") "AUG 2018 / Hören")
      )
      (libsource (lib "SCT8-Board1") (part "FDV303N"))
    )
    (comp (ref "Q46")
      (value "Q")
      (footprint "SOT23-3")
      (description "MOSFET N-CH 25V 680MA SOT-23")
      (fields
        (field (name "02. DISTRIBUTOR PART NUMBER") "FDV303NDKR-ND")
        (field (name "07. MANUFACTURER  PART NUMBER") "FDV303N")
        (field (name "13. CREATED DATE/NAME") "AUG 2018 / Hören")
      )
      (libsource (lib "SCT8-Board1") (part "FDV303N"))
    )
    (comp (ref "Q47")
      (value "Q")
      (footprint "SOT23-3")
      (description "MOSFET N-CH 25V 680MA SOT-23")
      (fields
        (field (name "02. DISTRIBUTOR PART NUMBER") "FDV303NDKR-ND")
        (field (name "07. MANUFACTURER  PART NUMBER") "FDV303N")
        (field (name "13. CREATED DATE/NAME") "AUG 2018 / Hören")
      )
      (libsource (lib "SCT8-Board1") (part "FDV303N"))
    )
    (comp (ref "Q48")
      (value "Q")
      (footprint "SOT23-3")
      (description "MOSFET N-CH 25V 680MA SOT-23")
      (fields
        (field (name "02. DISTRIBUTOR PART NUMBER") "FDV303NDKR-ND")
        (field (name "07. MANUFACTURER  PART NUMBER") "FDV303N")
        (field (name "13. CREATED DATE/NAME") "AUG 2018 / Hören")
      )
      (libsource (lib "SCT8-Board1") (part "FDV303N"))
    )
    (comp (ref "R1")
      (value "4K7")
      (footprint "R0402 Reflow")
      (description "Resistor")
      (fields
        (field (name "TOLERANCE") "±1%")
        (field (name "Comment") "R")
        (field (name "13. CREATED DATE/NAME") "AUG2018/Hören")
      )
      (libsource (lib "chickenfood") (part "R"))
    )
    (comp (ref "R2")
      (value "4K7")
      (footprint "R0402 Reflow")
      (description "Resistor")
      (fields
        (field (name "TOLERANCE") "±1%")
        (field (name "Comment") "R")
        (field (name "13. CREATED DATE/NAME") "AUG2018/Hören")
      )
      (libsource (lib "chickenfood") (part "R"))
    )
    (comp (ref "R3")
      (value "4K7")
      (footprint "R0402 Reflow")
      (description "Resistor")
      (fields
        (field (name "TOLERANCE") "±1%")
        (field (name "Comment") "R")
        (field (name "13. CREATED DATE/NAME") "AUG2018/Hören")
      )
      (libsource (lib "chickenfood") (part "R"))
    )
    (comp (ref "R4")
      (value "4K7")
      (footprint "R0402 Reflow")
      (description "Resistor")
      (fields
        (field (name "TOLERANCE") "±1%")
        (field (name "Comment") "R")
        (field (name "13. CREATED DATE/NAME") "AUG2018/Hören")
      )
      (libsource (lib "chickenfood") (part "R"))
    )
    (comp (ref "R5")
      (value "4K7")
      (footprint "R0402 Reflow")
      (description "Resistor")
      (fields
        (field (name "TOLERANCE") "±1%")
        (field (name "Comment") "R")
        (field (name "13. CREATED DATE/NAME") "AUG2018/Hören")
      )
      (libsource (lib "chickenfood") (part "R"))
    )
    (comp (ref "R6")
      (value "4K7")
      (footprint "R0402 Reflow")
      (description "Resistor")
      (fields
        (field (name "TOLERANCE") "±1%")
        (field (name "Comment") "R")
        (field (name "13. CREATED DATE/NAME") "AUG2018/Hören")
      )
      (libsource (lib "chickenfood") (part "R"))
    )
    (comp (ref "R7")
      (value "4K7")
      (footprint "R0402 Reflow")
      (description "Resistor")
      (fields
        (field (name "TOLERANCE") "±1%")
        (field (name "Comment") "R")
        (field (name "13. CREATED DATE/NAME") "AUG2018/Hören")
      )
      (libsource (lib "chickenfood") (part "R"))
    )
    (comp (ref "R8")
      (value "4K7")
      (footprint "R0402 Reflow")
      (description "Resistor")
      (fields
        (field (name "TOLERANCE") "±1%")
        (field (name "Comment") "R")
        (field (name "13. CREATED DATE/NAME") "AUG2018/Hören")
      )
      (libsource (lib "chickenfood") (part "R"))
    )
    (comp (ref "R9")
      (value "4K7")
      (footprint "R0402 Reflow")
      (description "Resistor")
      (fields
        (field (name "TOLERANCE") "±1%")
        (field (name "Comment") "R")
        (field (name "13. CREATED DATE/NAME") "AUG2018/Hören")
      )
      (libsource (lib "chickenfood") (part "R"))
    )
    (comp (ref "R10")
      (value "4K7")
      (footprint "R0402 Reflow")
      (description "Resistor")
      (fields
        (field (name "TOLERANCE") "±1%")
        (field (name "Comment") "R")
        (field (name "13. CREATED DATE/NAME") "AUG2018/Hören")
      )
      (libsource (lib "chickenfood") (part "R"))
    )
    (comp (ref "R11")
      (value "4K7")
      (footprint "R0402 Reflow")
      (description "Resistor")
      (fields
        (field (name "TOLERANCE") "±1%")
        (field (name "Comment") "R")
        (field (name "13. CREATED DATE/NAME") "AUG2018/Hören")
      )
      (libsource (lib "chickenfood") (part "R"))
    )
    (comp (ref "R12")
      (value "4K7")
      (footprint "R0402 Reflow")
      (description "Resistor")
      (fields
        (field (name "TOLERANCE") "±1%")
        (field (name "Comment") "R")
        (field (name "13. CREATED DATE/NAME") "AUG2018/Hören")
      )
      (libsource (lib "chickenfood") (part "R"))
    )
    (comp (ref "R13")
      (value "4K7")
      (footprint "R0402 Reflow")
      (description "Resistor")
      (fields
        (field (name "TOLERANCE") "±1%")
        (field (name "Comment") "R")
        (field (name "13. CREATED DATE/NAME") "AUG2018/Hören")
      )
      (libsource (lib "chickenfood") (part "R"))
    )
    (comp (ref "R14")
      (value "4K7")
      (footprint "R0402 Reflow")
      (description "Resistor")
      (fields
        (field (name "TOLERANCE") "±1%")
        (field (name "Comment") "R")
        (field (name "13. CREATED DATE/NAME") "AUG2018/Hören")
      )
      (libsource (lib "chickenfood") (part "R"))
    )
    (comp (ref "R15")
      (value "4K7")
      (footprint "R0402 Reflow")
      (description "Resistor")
      (fields
        (field (name "TOLERANCE") "±1%")
        (field (name "Comment") "R")
        (field (name "13. CREATED DATE/NAME") "AUG2018/Hören")
      )
      (libsource (lib "chickenfood") (part "R"))
    )
    (comp (ref "R16")
      (value "4K7")
      (footprint "R0402 Reflow")
      (description "Resistor")
      (fields
        (field (name "TOLERANCE") "±1%")
        (field (name "Comment") "R")
        (field (name "13. CREATED DATE/NAME") "AUG2018/Hören")
      )
      (libsource (lib "chickenfood") (part "R"))
    )
    (comp (ref "R17")
      (value "4K7")
      (footprint "R0402 Reflow")
      (description "Resistor")
      (fields
        (field (name "TOLERANCE") "±1%")
        (field (name "Comment") "R")
        (field (name "13. CREATED DATE/NAME") "AUG2018/Hören")
      )
      (libsource (lib "chickenfood") (part "R"))
    )
    (comp (ref "R18")
      (value "4K7")
      (footprint "R0402 Reflow")
      (description "Resistor")
      (fields
        (field (name "TOLERANCE") "±1%")
        (field (name "Comment") "R")
        (field (name "13. CREATED DATE/NAME") "AUG2018/Hören")
      )
      (libsource (lib "chickenfood") (part "R"))
    )
    (comp (ref "R19")
      (value "4K7")
      (footprint "R0402 Reflow")
      (description "Resistor")
      (fields
        (field (name "TOLERANCE") "±1%")
        (field (name "Comment") "R")
        (field (name "13. CREATED DATE/NAME") "AUG2018/Hören")
      )
      (libsource (lib "chickenfood") (part "R"))
    )
    (comp (ref "R20")
      (value "4K7")
      (footprint "R0402 Reflow")
      (description "Resistor")
      (fields
        (field (name "TOLERANCE") "±1%")
        (field (name "Comment") "R")
        (field (name "13. CREATED DATE/NAME") "AUG2018/Hören")
      )
      (libsource (lib "chickenfood") (part "R"))
    )
    (comp (ref "R21")
      (value "4K7")
      (footprint "R0402 Reflow")
      (description "Resistor")
      (fields
        (field (name "TOLERANCE") "±1%")
        (field (name "Comment") "R")
        (field (name "13. CREATED DATE/NAME") "AUG2018/Hören")
      )
      (libsource (lib "chickenfood") (part "R"))
    )
    (comp (ref "R22")
      (value "4K7")
      (footprint "R0402 Reflow")
      (description "Resistor")
      (fields
        (field (name "TOLERANCE") "±1%")
        (field (name "Comment") "R")
        (field (name "13. CREATED DATE/NAME") "AUG2018/Hören")
      )
      (libsource (lib "chickenfood") (part "R"))
    )
    (comp (ref "R23")
      (value "4K7")
      (footprint "R0402 Reflow")
      (description "Resistor")
      (fields
        (field (name "TOLERANCE") "±1%")
        (field (name "Comment") "R")
        (field (name "13. CREATED DATE/NAME") "AUG2018/Hören")
      )
      (libsource (lib "chickenfood") (part "R"))
    )
    (comp (ref "R24")
      (value "4K7")
      (footprint "R0402 Reflow")
      (description "Resistor")
      (fields
        (field (name "TOLERANCE") "±1%")
        (field (name "Comment") "R")
        (field (name "13. CREATED DATE/NAME") "AUG2018/Hören")
      )
      (libsource (lib "chickenfood") (part "R"))
    )
    (comp (ref "R25")
      (value "4K7")
      (footprint "R0402 Reflow")
      (description "Resistor")
      (fields
        (field (name "TOLERANCE") "±1%")
        (field (name "Comment") "R")
        (field (name "13. CREATED DATE/NAME") "AUG2018/Hören")
      )
      (libsource (lib "chickenfood") (part "R"))
    )
    (comp (ref "R26")
      (value "4K7")
      (footprint "R0402 Reflow")
      (description "Resistor")
      (fields
        (field (name "TOLERANCE") "±1%")
        (field (name "Comment") "R")
        (field (name "13. CREATED DATE/NAME") "AUG2018/Hören")
      )
      (libsource (lib "chickenfood") (part "R"))
    )
    (comp (ref "R27")
      (value "4K7")
      (footprint "R0402 Reflow")
      (description "Resistor")
      (fields
        (field (name "TOLERANCE") "±1%")
        (field (name "Comment") "R")
        (field (name "13. CREATED DATE/NAME") "AUG2018/Hören")
      )
      (libsource (lib "chickenfood") (part "R"))
    )
    (comp (ref "R28")
      (value "4K7")
      (footprint "R0402 Reflow")
      (description "Resistor")
      (fields
        (field (name "TOLERANCE") "±1%")
        (field (name "Comment") "R")
        (field (name "13. CREATED DATE/NAME") "AUG2018/Hören")
      )
      (libsource (lib "chickenfood") (part "R"))
    )
    (comp (ref "R29")
      (value "4K7")
      (footprint "R0402 Reflow")
      (description "Resistor")
      (fields
        (field (name "TOLERANCE") "±1%")
        (field (name "Comment") "R")
        (field (name "13. CREATED DATE/NAME") "AUG2018/Hören")
      )
      (libsource (lib "chickenfood") (part "R"))
    )
    (comp (ref "R30")
      (value "4K7")
      (footprint "R0402 Reflow")
      (description "Resistor")
      (fields
        (field (name "TOLERANCE") "±1%")
        (field (name "Comment") "R")
        (field (name "13. CREATED DATE/NAME") "AUG2018/Hören")
      )
      (libsource (lib "chickenfood") (part "R"))
    )
    (comp (ref "R31")
      (value "4K7")
      (footprint "R0402 Reflow")
      (description "Resistor")
      (fields
        (field (name "TOLERANCE") "±1%")
        (field (name "Comment") "R")
        (field (name "13. CREATED DATE/NAME") "AUG2018/Hören")
      )
      (libsource (lib "chickenfood") (part "R"))
    )
    (comp (ref "R32")
      (value "4K7")
      (footprint "R0402 Reflow")
      (description "Resistor")
      (fields
        (field (name "TOLERANCE") "±1%")
        (field (name "Comment") "R")
        (field (name "13. CREATED DATE/NAME") "AUG2018/Hören")
      )
      (libsource (lib "chickenfood") (part "R"))
    )
    (comp (ref "R33")
      (value "4K7")
      (footprint "R0402 Reflow")
      (description "Resistor")
      (fields
        (field (name "TOLERANCE") "±1%")
        (field (name "Comment") "R")
        (field (name "13. CREATED DATE/NAME") "AUG2018/Hören")
      )
      (libsource (lib "chickenfood") (part "R"))
    )
    (comp (ref "R34")
      (value "4K7")
      (footprint "R0402 Reflow")
      (description "Resistor")
      (fields
        (field (name "TOLERANCE") "±1%")
        (field (name "Comment") "R")
        (field (name "13. CREATED DATE/NAME") "AUG2018/Hören")
      )
      (libsource (lib "chickenfood") (part "R"))
    )
    (comp (ref "R35")
      (value "4K7")
      (footprint "R0402 Reflow")
      (description "Resistor")
      (fields
        (field (name "TOLERANCE") "±1%")
        (field (name "Comment") "R")
        (field (name "13. CREATED DATE/NAME") "AUG2018/Hören")
      )
      (libsource (lib "chickenfood") (part "R"))
    )
    (comp (ref "R36")
      (value "4K7")
      (footprint "R0402 Reflow")
      (description "Resistor")
      (fields
        (field (name "TOLERANCE") "±1%")
        (field (name "Comment") "R")
        (field (name "13. CREATED DATE/NAME") "AUG2018/Hören")
      )
      (libsource (lib "chickenfood") (part "R"))
    )
    (comp (ref "R37")
      (value "4K7")
      (footprint "R0402 Reflow")
      (description "Resistor")
      (fields
        (field (name "TOLERANCE") "±1%")
        (field (name "Comment") "R")
        (field (name "13. CREATED DATE/NAME") "AUG2018/Hören")
      )
      (libsource (lib "chickenfood") (part "R"))
    )
    (comp (ref "R38")
      (value "4K7")
      (footprint "R0402 Reflow")
      (description "Resistor")
      (fields
        (field (name "TOLERANCE") "±1%")
        (field (name "Comment") "R")
        (field (name "13. CREATED DATE/NAME") "AUG2018/Hören")
      )
      (libsource (lib "chickenfood") (part "R"))
    )
    (comp (ref "R39")
      (value "4K7")
      (footprint "R0402 Reflow")
      (description "Resistor")
      (fields
        (field (name "TOLERANCE") "±1%")
        (field (name "Comment") "R")
        (field (name "13. CREATED DATE/NAME") "AUG2018/Hören")
      )
      (libsource (lib "chickenfood") (part "R"))
    )
    (comp (ref "R40")
      (value "4K7")
      (footprint "R0402 Reflow")
      (description "Resistor")
      (fields
        (field (name "TOLERANCE") "±1%")
        (field (name "Comment") "R")
        (field (name "13. CREATED DATE/NAME") "AUG2018/Hören")
      )
      (libsource (lib "chickenfood") (part "R"))
    )
    (comp (ref "R41")
      (value "4K7")
      (footprint "R0402 Reflow")
      (description "Resistor")
      (fields
        (field (name "TOLERANCE") "±1%")
        (field (name "Comment") "R")
        (field (name "13. CREATED DATE/NAME") "AUG2018/Hören")
      )
      (libsource (lib "chickenfood") (part "R"))
    )
    (comp (ref "R42")
      (value "4K7")
      (footprint "R0402 Reflow")
      (description "Resistor")
      (fields
        (field (name "TOLERANCE") "±1%")
        (field (name "Comment") "R")
        (field (name "13. CREATED DATE/NAME") "AUG2018/Hören")
      )
      (libsource (lib "chickenfood") (part "R"))
    )
    (comp (ref "R48")
      (value "4K7")
      (footprint "R0402 Reflow")
      (description "Resistor")
      (fields
        (field (name "TOLERANCE") "±1%")
        (field (name "Comment") "R")
        (field (name "13. CREATED DATE/NAME") "AUG2018/Hören")
      )
      (libsource (lib "chickenfood") (part "R"))
    )
    (comp (ref "R49")
      (value "4K7")
      (footprint "R0402 Reflow")
      (description "Resistor")
      (fields
        (field (name "TOLERANCE") "±1%")
        (field (name "Comment") "R")
        (field (name "13. CREATED DATE/NAME") "AUG2018/Hören")
      )
      (libsource (lib "chickenfood") (part "R"))
    )
    (comp (ref "R50")
      (value "4K7")
      (footprint "R0402 Reflow")
      (description "Resistor")
      (fields
        (field (name "TOLERANCE") "±1%")
        (field (name "Comment") "R")
        (field (name "13. CREATED DATE/NAME") "AUG2018/Hören")
      )
      (libsource (lib "chickenfood") (part "R"))
    )
    (comp (ref "R51")
      (value "4K7")
      (footprint "R0402 Reflow")
      (description "Resistor")
      (fields
        (field (name "TOLERANCE") "±1%")
        (field (name "Comment") "R")
        (field (name "13. CREATED DATE/NAME") "AUG2018/Hören")
      )
      (libsource (lib "chickenfood") (part "R"))
    )
    (comp (ref "R52")
      (value "4K7")
      (footprint "R0402 Reflow")
      (description "Resistor")
      (fields
        (field (name "TOLERANCE") "±1%")
        (field (name "Comment") "R")
        (field (name "13. CREATED DATE/NAME") "AUG2018/Hören")
      )
      (libsource (lib "chickenfood") (part "R"))
    )
    (comp (ref "R53")
      (value "4K7")
      (footprint "R0402 Reflow")
      (description "Resistor")
      (fields
        (field (name "TOLERANCE") "±1%")
        (field (name "Comment") "R")
        (field (name "13. CREATED DATE/NAME") "AUG2018/Hören")
      )
      (libsource (lib "chickenfood") (part "R"))
    )
    (comp (ref "X1")
      (value "X")
      (description "24 x 2 x 1.27mm SOCKET DISCRETE CABL")
      (fields
        (field (name "02. DISTRIBUTOR PART NUMBER") "SFSD-24-30C-G-15.00-S")
        (field (name "13. CREATED DATE/NAME") "??? / Hören")
      )
      (libsource (lib "Connectors") (part "SFSD-24-30C-G-15.00-S"))
    )
    (comp (ref "X2")
      (value "X")
      (footprint "TFC-124-01-F-D-RA")
      (description "CONN HEADER TH RA 48POS 1.27MM")
      (fields
        (field (name "02. DISTRIBUTOR PART NUMBER") "TFC-124-01-F-D-RA")
        (field (name "13. CREATED DATE/NAME") "??? / Hören")
      )
      (libsource (lib "Connectors") (part "TFC-124-01-F-D-RA"))
    )
    (comp (ref "X3")
      (value "X")
      (footprint "CONFIG48")
      (description "PCB Tester Configuration Matrix for 48 Relays over 8 ABUSes")
      (fields (field (name "13. CREATED DATE/NAME") "??? / Hören"))
      (libsource (lib "Connectors") (part "CONFIG48"))
    )
    (comp (ref "X4")
      (value "X")
      (footprint "PCIE-036-02-F-D-Fingers")
      (description "CONN PCI Card Edge 36POS")
      (libsource (lib "Connectors") (part "PCIE-036-02-F-D-Fingers"))
    )
  )
  (nets
    (net (code "3") (name "/A0") (class "Default")
      (node (ref "X4") (pin "B1") (pinfunction "B1_B1") (pintype "passive"))
    )
    (net (code "4") (name "/A1") (class "Default")
      (node (ref "X4") (pin "B2") (pinfunction "B2_B2") (pintype "passive"))
    )
    (net (code "5") (name "/A2") (class "Default")
      (node (ref "X4") (pin "B3") (pinfunction "B3_B3") (pintype "passive"))
    )
    (net (code "6") (name "/A3") (class "Default")
      (node (ref "X4") (pin "B4") (pinfunction "B4_B4") (pintype "passive"))
    )
    (net (code "7") (name "/ABUS0") (class "Default")
      (node (ref "X3") (pin "ABUS0") (pinfunction "ABUS0_ABUS0") (pintype "passive"))
      (node (ref "X4") (pin "A1") (pinfunction "A1_A1") (pintype "passive"))
    )
    (net (code "8") (name "/ABUS1") (class "Default")
      (node (ref "X3") (pin "ABUS1") (pinfunction "ABUS1_ABUS1") (pintype "passive"))
      (node (ref "X4") (pin "A2") (pinfunction "A2_A2") (pintype "passive"))
    )
    (net (code "9") (name "/ABUS2") (class "Default")
      (node (ref "X3") (pin "ABUS2") (pinfunction "ABUS2_ABUS2") (pintype "passive"))
      (node (ref "X4") (pin "A3") (pinfunction "A3_A3") (pintype "passive"))
    )
    (net (code "10") (name "/ABUS3") (class "Default")
      (node (ref "X3") (pin "ABUS3") (pinfunction "ABUS3_ABUS3") (pintype "passive"))
      (node (ref "X4") (pin "A4") (pinfunction "A4_A4") (pintype "passive"))
    )
    (net (code "11") (name "/ABUS4") (class "Default")
      (node (ref "X3") (pin "ABUS4") (pinfunction "ABUS4_ABUS4") (pintype "passive"))
      (node (ref "X4") (pin "A5") (pinfunction "A5_A5") (pintype "passive"))
    )
    (net (code "12") (name "/ABUS5") (class "Default")
      (node (ref "X3") (pin "ABUS5") (pinfunction "ABUS5_ABUS5") (pintype "passive"))
      (node (ref "X4") (pin "A6") (pinfunction "A6_A6") (pintype "passive"))
    )
    (net (code "13") (name "/ABUS6") (class "Default")
      (node (ref "X3") (pin "ABUS6") (pinfunction "ABUS6_ABUS6") (pintype "passive"))
      (node (ref "X4") (pin "A7") (pinfunction "A7_A7") (pintype "passive"))
    )
    (net (code "14") (name "/ABUS7") (class "Default")
      (node (ref "X3") (pin "ABUS7") (pinfunction "ABUS7_ABUS7") (pintype "passive"))
      (node (ref "X4") (pin "A8") (pinfunction "A8_A8") (pintype "passive"))
    )
    (net (code "16") (name "/CS") (class "Default")
      (node (ref "X4") (pin "B18") (pinfunction "B18_B18") (pintype "passive"))
    )
    (net (code "17") (name "/DRV1") (class "Default")
      (node (ref "Q1") (pin "1") (pinfunction "G_1") (pintype "passive"))
      (node (ref "R1") (pin "2") (pinfunction "2_2") (pintype "passive"))
    )
    (net (code "18") (name "/DRV2") (class "Default")
      (node (ref "Q2") (pin "1") (pinfunction "G_1") (pintype "passive"))
      (node (ref "R2") (pin "2") (pinfunction "2_2") (pintype "passive"))
    )
    (net (code "19") (name "/DRV3") (class "Default")
      (node (ref "Q3") (pin "1") (pinfunction "G_1") (pintype "passive"))
      (node (ref "R3") (pin "2") (pinfunction "2_2") (pintype "passive"))
    )
    (net (code "20") (name "/DRV4") (class "Default")
      (node (ref "Q4") (pin "1") (pinfunction "G_1") (pintype "passive"))
      (node (ref "R4") (pin "2") (pinfunction "2_2") (pintype "passive"))
    )
    (net (code "21") (name "/DRV5") (class "Default")
      (node (ref "Q5") (pin "1") (pinfunction "G_1") (pintype "passive"))
      (node (ref "R5") (pin "2") (pinfunction "2_2") (pintype "passive"))
    )
    (net (code "22") (name "/DRV6") (class "Default")
      (node (ref "Q6") (pin "1") (pinfunction "G_1") (pintype "passive"))
      (node (ref "R6") (pin "2") (pinfunction "2_2") (pintype "passive"))
    )
    (net (code "23") (name "/DRV7") (class "Default")
      (node (ref "Q7") (pin "1") (pinfunction "G_1") (pintype "passive"))
      (node (ref "R7") (pin "2") (pinfunction "2_2") (pintype "passive"))
    )
    (net (code "24") (name "/DRV8") (class "Default")
      (node (ref "Q8") (pin "1") (pinfunction "G_1") (pintype "passive"))
      (node (ref "R8") (pin "2") (pinfunction "2_2") (pintype "passive"))
    )
    (net (code "25") (name "/DRV9") (class "Default")
      (node (ref "Q9") (pin "1") (pinfunction "G_1") (pintype "passive"))
      (node (ref "R9") (pin "2") (pinfunction "2_2") (pintype "passive"))
    )
    (net (code "26") (name "/DRV10") (class "Default")
      (node (ref "Q10") (pin "1") (pinfunction "G_1") (pintype "passive"))
      (node (ref "R10") (pin "2") (pinfunction "2_2") (pintype "passive"))
    )
    (net (code "27") (name "/DRV11") (class "Default")
      (node (ref "Q11") (pin "1") (pinfunction "G_1") (pintype "passive"))
      (node (ref "R11") (pin "2") (pinfunction "2_2") (pintype "passive"))
    )
    (net (code "28") (name "/DRV12") (class "Default")
      (node (ref "Q12") (pin "1") (pinfunction "G_1") (pintype "passive"))
      (node (ref "R12") (pin "2") (pinfunction "2_2") (pintype "passive"))
    )
    (net (code "29") (name "/DRV13") (class "Default")
      (node (ref "Q13") (pin "1") (pinfunction "G_1") (pintype "passive"))
      (node (ref "R13") (pin "2") (pinfunction "2_2") (pintype "passive"))
    )
    (net (code "30") (name "/DRV14") (class "Default")
      (node (ref "Q14") (pin "1") (pinfunction "G_1") (pintype "passive"))
      (node (ref "R14") (pin "2") (pinfunction "2_2") (pintype "passive"))
    )
    (net (code "31") (name "/DRV15") (class "Default")
      (node (ref "Q15") (pin "1") (pinfunction "G_1") (pintype "passive"))
      (node (ref "R15") (pin "2") (pinfunction "2_2") (pintype "passive"))
    )
    (net (code "32") (name "/DRV16") (class "Default")
      (node (ref "Q16") (pin "1") (pinfunction "G_1") (pintype "passive"))
      (node (ref "R16") (pin "2") (pinfunction "2_2") (pintype "passive"))
    )
    (net (code "33") (name "/DRV17") (class "Default")
      (node (ref "Q17") (pin "1") (pinfunction "G_1") (pintype "passive"))
      (node (ref "R17") (pin "2") (pinfunction "2_2") (pintype "passive"))
    )
    (net (code "34") (name "/DRV18") (class "Default")
      (node (ref "Q18") (pin "1") (pinfunction "G_1") (pintype "passive"))
      (node (ref "R18") (pin "2") (pinfunction "2_2") (pintype "passive"))
    )
    (net (code "35") (name "/DRV19") (class "Default")
      (node (ref "Q19") (pin "1") (pinfunction "G_1") (pintype "passive"))
      (node (ref "R19") (pin "2") (pinfunction "2_2") (pintype "passive"))
    )
    (net (code "36") (name "/DRV20") (class "Default")
      (node (ref "Q20") (pin "1") (pinfunction "G_1") (pintype "passive"))
      (node (ref "R20") (pin "2") (pinfunction "2_2") (pintype "passive"))
    )
    (net (code "37") (name "/DRV21") (class "Default")
      (node (ref "Q21") (pin "1") (pinfunction "G_1") (pintype "passive"))
      (node (ref "R21") (pin "2") (pinfunction "2_2") (pintype "passive"))
    )
    (net (code "38") (name "/DRV22") (class "Default")
      (node (ref "Q22") (pin "1") (pinfunction "G_1") (pintype "passive"))
      (node (ref "R22") (pin "2") (pinfunction "2_2") (pintype "passive"))
    )
    (net (code "39") (name "/DRV23") (class "Default")
      (node (ref "Q23") (pin "1") (pinfunction "G_1") (pintype "passive"))
      (node (ref "R23") (pin "2") (pinfunction "2_2") (pintype "passive"))
    )
    (net (code "40") (name "/DRV24") (class "Default")
      (node (ref "Q24") (pin "1") (pinfunction "G_1") (pintype "passive"))
      (node (ref "R24") (pin "2") (pinfunction "2_2") (pintype "passive"))
    )
    (net (code "41") (name "/DRV25") (class "Default")
      (node (ref "Q25") (pin "1") (pinfunction "G_1") (pintype "passive"))
      (node (ref "R25") (pin "2") (pinfunction "2_2") (pintype "passive"))
    )
    (net (code "42") (name "/DRV26") (class "Default")
      (node (ref "Q26") (pin "1") (pinfunction "G_1") (pintype "passive"))
      (node (ref "R26") (pin "2") (pinfunction "2_2") (pintype "passive"))
    )
    (net (code "43") (name "/DRV27") (class "Default")
      (node (ref "Q27") (pin "1") (pinfunction "G_1") (pintype "passive"))
      (node (ref "R27") (pin "2") (pinfunction "2_2") (pintype "passive"))
    )
    (net (code "44") (name "/DRV28") (class "Default")
      (node (ref "Q28") (pin "1") (pinfunction "G_1") (pintype "passive"))
      (node (ref "R28") (pin "2") (pinfunction "2_2") (pintype "passive"))
    )
    (net (code "45") (name "/DRV29") (class "Default")
      (node (ref "Q29") (pin "1") (pinfunction "G_1") (pintype "passive"))
      (node (ref "R29") (pin "2") (pinfunction "2_2") (pintype "passive"))
    )
    (net (code "46") (name "/DRV30") (class "Default")
      (node (ref "Q30") (pin "1") (pinfunction "G_1") (pintype "passive"))
      (node (ref "R30") (pin "2") (pinfunction "2_2") (pintype "passive"))
    )
    (net (code "47") (name "/DRV31") (class "Default")
      (node (ref "Q31") (pin "1") (pinfunction "G_1") (pintype "passive"))
      (node (ref "R31") (pin "2") (pinfunction "2_2") (pintype "passive"))
    )
    (net (code "48") (name "/DRV32") (class "Default")
      (node (ref "Q32") (pin "1") (pinfunction "G_1") (pintype "passive"))
      (node (ref "R32") (pin "2") (pinfunction "2_2") (pintype "passive"))
    )
    (net (code "49") (name "/DRV33") (class "Default")
      (node (ref "Q33") (pin "1") (pinfunction "G_1") (pintype "passive"))
      (node (ref "R33") (pin "2") (pinfunction "2_2") (pintype "passive"))
    )
    (net (code "50") (name "/DRV34") (class "Default")
      (node (ref "Q34") (pin "1") (pinfunction "G_1") (pintype "passive"))
      (node (ref "R34") (pin "2") (pinfunction "2_2") (pintype "passive"))
    )
    (net (code "51") (name "/DRV35") (class "Default")
      (node (ref "Q35") (pin "1") (pinfunction "G_1") (pintype "passive"))
      (node (ref "R35") (pin "2") (pinfunction "2_2") (pintype "passive"))
    )
    (net (code "52") (name "/DRV36") (class "Default")
      (node (ref "Q36") (pin "1") (pinfunction "G_1") (pintype "passive"))
      (node (ref "R36") (pin "2") (pinfunction "2_2") (pintype "passive"))
    )
    (net (code "53") (name "/DRV37") (class "Default")
      (node (ref "Q37") (pin "1") (pinfunction "G_1") (pintype "passive"))
      (node (ref "R37") (pin "2") (pinfunction "2_2") (pintype "passive"))
    )
    (net (code "54") (name "/DRV38") (class "Default")
      (node (ref "Q38") (pin "1") (pinfunction "G_1") (pintype "passive"))
      (node (ref "R38") (pin "2") (pinfunction "2_2") (pintype "passive"))
    )
    (net (code "55") (name "/DRV39") (class "Default")
      (node (ref "Q39") (pin "1") (pinfunction "G_1") (pintype "passive"))
      (node (ref "R39") (pin "2") (pinfunction "2_2") (pintype "passive"))
    )
    (net (code "56") (name "/DRV40") (class "Default")
      (node (ref "Q40") (pin "1") (pinfunction "G_1") (pintype "passive"))
      (node (ref "R40") (pin "2") (pinfunction "2_2") (pintype "passive"))
    )
    (net (code "57") (name "/DRV41") (class "Default")
      (node (ref "Q41") (pin "1") (pinfunction "G_1") (pintype "passive"))
      (node (ref "R41") (pin "2") (pinfunction "2_2") (pintype "passive"))
    )
    (net (code "58") (name "/DRV42") (class "Default")
      (node (ref "Q42") (pin "1") (pinfunction "G_1") (pintype "passive"))
      (node (ref "R42") (pin "2") (pinfunction "2_2") (pintype "passive"))
    )
    (net (code "59") (name "/DRV43") (class "Default")
      (node (ref "Q43") (pin "1") (pinfunction "G_1") (pintype "passive"))
      (node (ref "R48") (pin "2") (pinfunction "2_2") (pintype "passive"))
    )
    (net (code "60") (name "/DRV44") (class "Default")
      (node (ref "Q44") (pin "1") (pinfunction "G_1") (pintype "passive"))
      (node (ref "R49") (pin "2") (pinfunction "2_2") (pintype "passive"))
    )
    (net (code "61") (name "/DRV45") (class "Default")
      (node (ref "Q45") (pin "1") (pinfunction "G_1") (pintype "passive"))
      (node (ref "R50") (pin "2") (pinfunction "2_2") (pintype "passive"))
    )
    (net (code "62") (name "/DRV46") (class "Default")
      (node (ref "Q46") (pin "1") (pinfunction "G_1") (pintype "passive"))
      (node (ref "R51") (pin "2") (pinfunction "2_2") (pintype "passive"))
    )
    (net (code "63") (name "/DRV47") (class "Default")
      (node (ref "Q47") (pin "1") (pinfunction "G_1") (pintype "passive"))
      (node (ref "R52") (pin "2") (pinfunction "2_2") (pintype "passive"))
    )
    (net (code "64") (name "/DRV48") (class "Default")
      (node (ref "Q48") (pin "1") (pinfunction "G_1") (pintype "passive"))
      (node (ref "R53") (pin "2") (pinfunction "2_2") (pintype "passive"))
    )
    (net (code "66") (name "/MISO") (class "Default")
      (node (ref "X4") (pin "A18") (pinfunction "A18_A18") (pintype "passive"))
    )
    (net (code "67") (name "/MOSI") (class "Default")
      (node (ref "X4") (pin "A17") (pinfunction "A17_A17") (pintype "passive"))
    )
    (net (code "68") (name "/SCLK") (class "Default")
      (node (ref "X4") (pin "B17") (pinfunction "B17_B17") (pintype "passive"))
    )
    (net (code "71") (name "1V0") (class "Default")
      (node (ref "D1") (pin "1") (pinfunction "A_1") (pintype "passive"))
    )
    (net (code "72") (name "1V8") (class "Default")
      (node (ref "D1") (pin "2") (pinfunction "C_2") (pintype "passive"))
      (node (ref "D2") (pin "1") (pinfunction "A_1") (pintype "passive"))
    )
    (net (code "73") (name "2V5") (class "Default")
      (node (ref "D2") (pin "2") (pinfunction "C_2") (pintype "passive"))
      (node (ref "D3") (pin "1") (pinfunction "A_1") (pintype "passive"))
    )
    (net (code "74") (name "3V3") (class "Default")
      (node (ref "D3") (pin "2") (pinfunction "C_2") (pintype "passive"))
      (node (ref "D4") (pin "1") (pinfunction "A_1") (pintype "passive"))
    )
    (net (code "75") (name "5V0R") (class "Default")
      (node (ref "D4") (pin "2") (pinfunction "C_2") (pintype "passive"))
      (node (ref "K1") (pin "1") (pinfunction "+_1") (pintype "passive"))
      (node (ref "K10") (pin "1") (pinfunction "+_1") (pintype "passive"))
      (node (ref "K11") (pin "1") (pinfunction "+_1") (pintype "passive"))
      (node (ref "K12") (pin "1") (pinfunction "+_1") (pintype "passive"))
      (node (ref "K13") (pin "1") (pinfunction "+_1") (pintype "passive"))
      (node (ref "K14") (pin "1") (pinfunction "+_1") (pintype "passive"))
      (node (ref "K15") (pin "1") (pinfunction "+_1") (pintype "passive"))
      (node (ref "K16") (pin "1") (pinfunction "+_1") (pintype "passive"))
      (node (ref "K17") (pin "1") (pinfunction "+_1") (pintype "passive"))
      (node (ref "K18") (pin "1") (pinfunction "+_1") (pintype "passive"))
      (node (ref "K19") (pin "1") (pinfunction "+_1") (pintype "passive"))
      (node (ref "K2") (pin "1") (pinfunction "+_1") (pintype "passive"))
      (node (ref "K20") (pin "1") (pinfunction "+_1") (pintype "passive"))
      (node (ref "K21") (pin "1") (pinfunction "+_1") (pintype "passive"))
      (node (ref "K22") (pin "1") (pinfunction "+_1") (pintype "passive"))
      (node (ref "K23") (pin "1") (pinfunction "+_1") (pintype "passive"))
      (node (ref "K24") (pin "1") (pinfunction "+_1") (pintype "passive"))
      (node (ref "K25") (pin "1") (pinfunction "+_1") (pintype "passive"))
      (node (ref "K26") (pin "1") (pinfunction "+_1") (pintype "passive"))
      (node (ref "K27") (pin "1") (pinfunction "+_1") (pintype "passive"))
      (node (ref "K28") (pin "1") (pinfunction "+_1") (pintype "passive"))
      (node (ref "K29") (pin "1") (pinfunction "+_1") (pintype "passive"))
      (node (ref "K3") (pin "1") (pinfunction "+_1") (pintype "passive"))
      (node (ref "K30") (pin "1") (pinfunction "+_1") (pintype "passive"))
      (node (ref "K31") (pin "1") (pinfunction "+_1") (pintype "passive"))
      (node (ref "K32") (pin "1") (pinfunction "+_1") (pintype "passive"))
      (node (ref "K33") (pin "1") (pinfunction "+_1") (pintype "passive"))
      (node (ref "K34") (pin "1") (pinfunction "+_1") (pintype "passive"))
      (node (ref "K35") (pin "1") (pinfunction "+_1") (pintype "passive"))
      (node (ref "K36") (pin "1") (pinfunction "+_1") (pintype "passive"))
      (node (ref "K37") (pin "1") (pinfunction "+_1") (pintype "passive"))
      (node (ref "K38") (pin "1") (pinfunction "+_1") (pintype "passive"))
      (node (ref "K39") (pin "1") (pinfunction "+_1") (pintype "passive"))
      (node (ref "K4") (pin "1") (pinfunction "+_1") (pintype "passive"))
      (node (ref "K40") (pin "1") (pinfunction "+_1") (pintype "passive"))
      (node (ref "K41") (pin "1") (pinfunction "+_1") (pintype "passive"))
      (node (ref "K42") (pin "1") (pinfunction "+_1") (pintype "passive"))
      (node (ref "K43") (pin "1") (pinfunction "+_1") (pintype "passive"))
      (node (ref "K44") (pin "1") (pinfunction "+_1") (pintype "passive"))
      (node (ref "K45") (pin "1") (pinfunction "+_1") (pintype "passive"))
      (node (ref "K46") (pin "1") (pinfunction "+_1") (pintype "passive"))
      (node (ref "K47") (pin "1") (pinfunction "+_1") (pintype "passive"))
      (node (ref "K48") (pin "1") (pinfunction "+_1") (pintype "passive"))
      (node (ref "K5") (pin "1") (pinfunction "+_1") (pintype "passive"))
      (node (ref "K6") (pin "1") (pinfunction "+_1") (pintype "passive"))
      (node (ref "K7") (pin "1") (pinfunction "+_1") (pintype "passive"))
      (node (ref "K8") (pin "1") (pinfunction "+_1") (pintype "passive"))
      (node (ref "K9") (pin "1") (pinfunction "+_1") (pintype "passive"))
      (node (ref "X4") (pin "B10") (pinfunction "B10_B10") (pintype "passive"))
      (node (ref "X4") (pin "B11") (pinfunction "B11_B11") (pintype "passive"))
      (node (ref "X4") (pin "B12") (pinfunction "B12_B12") (pintype "passive"))
      (node (ref "X4") (pin "B13") (pinfunction "B13_B13") (pintype "passive"))
      (node (ref "X4") (pin "B14") (pinfunction "B14_B14") (pintype "passive"))
      (node (ref "X4") (pin "B15") (pinfunction "B15_B15") (pintype "passive"))
      (node (ref "X4") (pin "B16") (pinfunction "B16_B16") (pintype "passive"))
      (node (ref "X4") (pin "B9") (pinfunction "B9_B9") (pintype "passive"))
    )
    (net (code "76") (name "12V0") (class "Default")
      (node (ref "X4") (pin "B5") (pinfunction "B5_B5") (pintype "passive"))
      (node (ref "X4") (pin "B6") (pinfunction "B6_B6") (pintype "passive"))
      (node (ref "X4") (pin "B7") (pinfunction "B7_B7") (pintype "passive"))
      (node (ref "X4") (pin "B8") (pinfunction "B8_B8") (pintype "passive"))
    )
    (net (code "77") (name "GND") (class "Default")
      (node (ref "Q1") (pin "2") (pinfunction "S_2") (pintype "passive"))
      (node (ref "Q10") (pin "2") (pinfunction "S_2") (pintype "passive"))
      (node (ref "Q11") (pin "2") (pinfunction "S_2") (pintype "passive"))
      (node (ref "Q12") (pin "2") (pinfunction "S_2") (pintype "passive"))
      (node (ref "Q13") (pin "2") (pinfunction "S_2") (pintype "passive"))
      (node (ref "Q14") (pin "2") (pinfunction "S_2") (pintype "passive"))
      (node (ref "Q15") (pin "2") (pinfunction "S_2") (pintype "passive"))
      (node (ref "Q16") (pin "2") (pinfunction "S_2") (pintype "passive"))
      (node (ref "Q17") (pin "2") (pinfunction "S_2") (pintype "passive"))
      (node (ref "Q18") (pin "2") (pinfunction "S_2") (pintype "passive"))
      (node (ref "Q19") (pin "2") (pinfunction "S_2") (pintype "passive"))
      (node (ref "Q2") (pin "2") (pinfunction "S_2") (pintype "passive"))
      (node (ref "Q20") (pin "2") (pinfunction "S_2") (pintype "passive"))
      (node (ref "Q21") (pin "2") (pinfunction "S_2") (pintype "passive"))
      (node (ref "Q22") (pin "2") (pinfunction "S_2") (pintype "passive"))
      (node (ref "Q23") (pin "2") (pinfunction "S_2") (pintype "passive"))
      (node (ref "Q24") (pin "2") (pinfunction "S_2") (pintype "passive"))
      (node (ref "Q25") (pin "2") (pinfunction "S_2") (pintype "passive"))
      (node (ref "Q26") (pin "2") (pinfunction "S_2") (pintype "passive"))
      (node (ref "Q27") (pin "2") (pinfunction "S_2") (pintype "passive"))
      (node (ref "Q28") (pin "2") (pinfunction "S_2") (pintype "passive"))
      (node (ref "Q29") (pin "2") (pinfunction "S_2") (pintype "passive"))
      (node (ref "Q3") (pin "2") (pinfunction "S_2") (pintype "passive"))
      (node (ref "Q30") (pin "2") (pinfunction "S_2") (pintype "passive"))
      (node (ref "Q31") (pin "2") (pinfunction "S_2") (pintype "passive"))
      (node (ref "Q32") (pin "2") (pinfunction "S_2") (pintype "passive"))
      (node (ref "Q33") (pin "2") (pinfunction "S_2") (pintype "passive"))
      (node (ref "Q34") (pin "2") (pinfunction "S_2") (pintype "passive"))
      (node (ref "Q35") (pin "2") (pinfunction "S_2") (pintype "passive"))
      (node (ref "Q36") (pin "2") (pinfunction "S_2") (pintype "passive"))
      (node (ref "Q37") (pin "2") (pinfunction "S_2") (pintype "passive"))
      (node (ref "Q38") (pin "2") (pinfunction "S_2") (pintype "passive"))
      (node (ref "Q39") (pin "2") (pinfunction "S_2") (pintype "passive"))
      (node (ref "Q4") (pin "2") (pinfunction "S_2") (pintype "passive"))
      (node (ref "Q40") (pin "2") (pinfunction "S_2") (pintype "passive"))
      (node (ref "Q41") (pin "2") (pinfunction "S_2") (pintype "passive"))
      (node (ref "Q42") (pin "2") (pinfunction "S_2") (pintype "passive"))
      (node (ref "Q43") (pin "2") (pinfunction "S_2") (pintype "passive"))
      (node (ref "Q44") (pin "2") (pinfunction "S_2") (pintype "passive"))
      (node (ref "Q45") (pin "2") (pinfunction "S_2") (pintype "passive"))
      (node (ref "Q46") (pin "2") (pinfunction "S_2") (pintype "passive"))
      (node (ref "Q47") (pin "2") (pinfunction "S_2") (pintype "passive"))
      (node (ref "Q48") (pin "2") (pinfunction "S_2") (pintype "passive"))
      (node (ref "Q5") (pin "2") (pinfunction "S_2") (pintype "passive"))
      (node (ref "Q6") (pin "2") (pinfunction "S_2") (pintype "passive"))
      (node (ref "Q7") (pin "2") (pinfunction "S_2") (pintype "passive"))
      (node (ref "Q8") (pin "2") (pinfunction "S_2") (pintype "passive"))
      (node (ref "Q9") (pin "2") (pinfunction "S_2") (pintype "passive"))
      (node (ref "R1") (pin "1") (pinfunction "1_1") (pintype "passive"))
      (node (ref "R10") (pin "1") (pinfunction "1_1") (pintype "passive"))
      (node (ref "R11") (pin "1") (pinfunction "1_1") (pintype "passive"))
      (node (ref "R12") (pin "1") (pinfunction "1_1") (pintype "passive"))
      (node (ref "R13") (pin "1") (pinfunction "1_1") (pintype "passive"))
      (node (ref "R14") (pin "1") (pinfunction "1_1") (pintype "passive"))
      (node (ref "R15") (pin "1") (pinfunction "1_1") (pintype "passive"))
      (node (ref "R16") (pin "1") (pinfunction "1_1") (pintype "passive"))
      (node (ref "R17") (pin "1") (pinfunction "1_1") (pintype "passive"))
      (node (ref "R18") (pin "1") (pinfunction "1_1") (pintype "passive"))
      (node (ref "R19") (pin "1") (pinfunction "1_1") (pintype "passive"))
      (node (ref "R2") (pin "1") (pinfunction "1_1") (pintype "passive"))
      (node (ref "R20") (pin "1") (pinfunction "1_1") (pintype "passive"))
      (node (ref "R21") (pin "1") (pinfunction "1_1") (pintype "passive"))
      (node (ref "R22") (pin "1") (pinfunction "1_1") (pintype "passive"))
      (node (ref "R23") (pin "1") (pinfunction "1_1") (pintype "passive"))
      (node (ref "R24") (pin "1") (pinfunction "1_1") (pintype "passive"))
      (node (ref "R25") (pin "1") (pinfunction "1_1") (pintype "passive"))
      (node (ref "R26") (pin "1") (pinfunction "1_1") (pintype "passive"))
      (node (ref "R27") (pin "1") (pinfunction "1_1") (pintype "passive"))
      (node (ref "R28") (pin "1") (pinfunction "1_1") (pintype "passive"))
      (node (ref "R29") (pin "1") (pinfunction "1_1") (pintype "passive"))
      (node (ref "R3") (pin "1") (pinfunction "1_1") (pintype "passive"))
      (node (ref "R30") (pin "1") (pinfunction "1_1") (pintype "passive"))
      (node (ref "R31") (pin "1") (pinfunction "1_1") (pintype "passive"))
      (node (ref "R32") (pin "1") (pinfunction "1_1") (pintype "passive"))
      (node (ref "R33") (pin "1") (pinfunction "1_1") (pintype "passive"))
      (node (ref "R34") (pin "1") (pinfunction "1_1") (pintype "passive"))
      (node (ref "R35") (pin "1") (pinfunction "1_1") (pintype "passive"))
      (node (ref "R36") (pin "1") (pinfunction "1_1") (pintype "passive"))
      (node (ref "R37") (pin "1") (pinfunction "1_1") (pintype "passive"))
      (node (ref "R38") (pin "1") (pinfunction "1_1") (pintype "passive"))
      (node (ref "R39") (pin "1") (pinfunction "1_1") (pintype "passive"))
      (node (ref "R4") (pin "1") (pinfunction "1_1") (pintype "passive"))
      (node (ref "R40") (pin "1") (pinfunction "1_1") (pintype "passive"))
      (node (ref "R41") (pin "1") (pinfunction "1_1") (pintype "passive"))
      (node (ref "R42") (pin "1") (pinfunction "1_1") (pintype "passive"))
      (node (ref "R48") (pin "1") (pinfunction "1_1") (pintype "passive"))
      (node (ref "R49") (pin "1") (pinfunction "1_1") (pintype "passive"))
      (node (ref "R5") (pin "1") (pinfunction "1_1") (pintype "passive"))
      (node (ref "R50") (pin "1") (pinfunction "1_1") (pintype "passive"))
      (node (ref "R51") (pin "1") (pinfunction "1_1") (pintype "passive"))
      (node (ref "R52") (pin "1") (pinfunction "1_1") (pintype "passive"))
      (node (ref "R53") (pin "1") (pinfunction "1_1") (pintype "passive"))
      (node (ref "R6") (pin "1") (pinfunction "1_1") (pintype "passive"))
      (node (ref "R7") (pin "1") (pinfunction "1_1") (pintype "passive"))
      (node (ref "R8") (pin "1") (pinfunction "1_1") (pintype "passive"))
      (node (ref "R9") (pin "1") (pinfunction "1_1") (pintype "passive"))
      (node (ref "X4") (pin "A10") (pinfunction "A10_A10") (pintype "passive"))
      (node (ref "X4") (pin "A11") (pinfunction "A11_A11") (pintype "passive"))
      (node (ref "X4") (pin "A12") (pinfunction "A12_A12") (pintype "passive"))
      (node (ref "X4") (pin "A13") (pinfunction "A13_A13") (pintype "passive"))
      (node (ref "X4") (pin "A14") (pinfunction "A14_A14") (pintype "passive"))
      (node (ref "X4") (pin "A15") (pinfunction "A15_A15") (pintype "passive"))
      (node (ref "X4") (pin "A16") (pinfunction "A16_A16") (pintype "passive"))
      (node (ref "X4") (pin "A9") (pinfunction "A9_A9") (pintype "passive"))
    )
    (net (code "78") (name "Net-(K1A-CA)") (class "Default")
      (node (ref "K1") (pin "3") (pinfunction "CA_3") (pintype "passive"))
      (node (ref "X3") (pin "1") (pinfunction "1_1") (pintype "passive"))
    )
    (net (code "79") (name "Net-(K1A-CB)") (class "Default")
      (node (ref "K1") (pin "4") (pinfunction "CB_4") (pintype "passive"))
      (node (ref "X2") (pin "1") (pinfunction "1_1") (pintype "passive"))
    )
    (net (code "80") (name "Net-(K1B--)") (class "Default")
      (node (ref "K1") (pin "2") (pinfunction "-_2") (pintype "passive"))
      (node (ref "Q1") (pin "3") (pinfunction "D_3") (pintype "passive"))
    )
    (net (code "81") (name "Net-(K2A-CA)") (class "Default")
      (node (ref "K2") (pin "3") (pinfunction "CA_3") (pintype "passive"))
      (node (ref "X3") (pin "2") (pinfunction "2_2") (pintype "passive"))
    )
    (net (code "82") (name "Net-(K2A-CB)") (class "Default")
      (node (ref "K2") (pin "4") (pinfunction "CB_4") (pintype "passive"))
      (node (ref "X2") (pin "2") (pinfunction "2_2") (pintype "passive"))
    )
    (net (code "83") (name "Net-(K2B--)") (class "Default")
      (node (ref "K2") (pin "2") (pinfunction "-_2") (pintype "passive"))
      (node (ref "Q2") (pin "3") (pinfunction "D_3") (pintype "passive"))
    )
    (net (code "84") (name "Net-(K3A-CA)") (class "Default")
      (node (ref "K3") (pin "3") (pinfunction "CA_3") (pintype "passive"))
      (node (ref "X3") (pin "3") (pinfunction "3_3") (pintype "passive"))
    )
    (net (code "85") (name "Net-(K3A-CB)") (class "Default")
      (node (ref "K3") (pin "4") (pinfunction "CB_4") (pintype "passive"))
      (node (ref "X2") (pin "3") (pinfunction "3_3") (pintype "passive"))
    )
    (net (code "86") (name "Net-(K3B--)") (class "Default")
      (node (ref "K3") (pin "2") (pinfunction "-_2") (pintype "passive"))
      (node (ref "Q3") (pin "3") (pinfunction "D_3") (pintype "passive"))
    )
    (net (code "87") (name "Net-(K4A-CA)") (class "Default")
      (node (ref "K4") (pin "3") (pinfunction "CA_3") (pintype "passive"))
      (node (ref "X3") (pin "4") (pinfunction "4_4") (pintype "passive"))
    )
    (net (code "88") (name "Net-(K4A-CB)") (class "Default")
      (node (ref "K4") (pin "4") (pinfunction "CB_4") (pintype "passive"))
      (node (ref "X2") (pin "4") (pinfunction "4_4") (pintype "passive"))
    )
    (net (code "89") (name "Net-(K4B--)") (class "Default")
      (node (ref "K4") (pin "2") (pinfunction "-_2") (pintype "passive"))
      (node (ref "Q4") (pin "3") (pinfunction "D_3") (pintype "passive"))
    )
    (net (code "90") (name "Net-(K5A-CA)") (class "Default")
      (node (ref "K5") (pin "3") (pinfunction "CA_3") (pintype "passive"))
      (node (ref "X3") (pin "5") (pinfunction "5_5") (pintype "passive"))
    )
    (net (code "91") (name "Net-(K5A-CB)") (class "Default")
      (node (ref "K5") (pin "4") (pinfunction "CB_4") (pintype "passive"))
      (node (ref "X2") (pin "5") (pinfunction "5_5") (pintype "passive"))
    )
    (net (code "92") (name "Net-(K5B--)") (class "Default")
      (node (ref "K5") (pin "2") (pinfunction "-_2") (pintype "passive"))
      (node (ref "Q5") (pin "3") (pinfunction "D_3") (pintype "passive"))
    )
    (net (code "93") (name "Net-(K6A-CA)") (class "Default")
      (node (ref "K6") (pin "3") (pinfunction "CA_3") (pintype "passive"))
      (node (ref "X3") (pin "6") (pinfunction "6_6") (pintype "passive"))
    )
    (net (code "94") (name "Net-(K6A-CB)") (class "Default")
      (node (ref "K6") (pin "4") (pinfunction "CB_4") (pintype "passive"))
      (node (ref "X2") (pin "6") (pinfunction "6_6") (pintype "passive"))
    )
    (net (code "95") (name "Net-(K6B--)") (class "Default")
      (node (ref "K6") (pin "2") (pinfunction "-_2") (pintype "passive"))
      (node (ref "Q6") (pin "3") (pinfunction "D_3") (pintype "passive"))
    )
    (net (code "96") (name "Net-(K7A-CA)") (class "Default")
      (node (ref "K7") (pin "3") (pinfunction "CA_3") (pintype "passive"))
      (node (ref "X3") (pin "7") (pinfunction "7_7") (pintype "passive"))
    )
    (net (code "97") (name "Net-(K7A-CB)") (class "Default")
      (node (ref "K7") (pin "4") (pinfunction "CB_4") (pintype "passive"))
      (node (ref "X2") (pin "7") (pinfunction "7_7") (pintype "passive"))
    )
    (net (code "98") (name "Net-(K7B--)") (class "Default")
      (node (ref "K7") (pin "2") (pinfunction "-_2") (pintype "passive"))
      (node (ref "Q7") (pin "3") (pinfunction "D_3") (pintype "passive"))
    )
    (net (code "99") (name "Net-(K8A-CA)") (class "Default")
      (node (ref "K8") (pin "3") (pinfunction "CA_3") (pintype "passive"))
      (node (ref "X3") (pin "8") (pinfunction "8_8") (pintype "passive"))
    )
    (net (code "100") (name "Net-(K8A-CB)") (class "Default")
      (node (ref "K8") (pin "4") (pinfunction "CB_4") (pintype "passive"))
      (node (ref "X2") (pin "8") (pinfunction "8_8") (pintype "passive"))
    )
    (net (code "101") (name "Net-(K8B--)") (class "Default")
      (node (ref "K8") (pin "2") (pinfunction "-_2") (pintype "passive"))
      (node (ref "Q8") (pin "3") (pinfunction "D_3") (pintype "passive"))
    )
    (net (code "102") (name "Net-(K9A-CA)") (class "Default")
      (node (ref "K9") (pin "3") (pinfunction "CA_3") (pintype "passive"))
      (node (ref "X3") (pin "9") (pinfunction "9_9") (pintype "passive"))
    )
    (net (code "103") (name "Net-(K9A-CB)") (class "Default")
      (node (ref "K9") (pin "4") (pinfunction "CB_4") (pintype "passive"))
      (node (ref "X2") (pin "9") (pinfunction "9_9") (pintype "passive"))
    )
    (net (code "104") (name "Net-(K9B--)") (class "Default")
      (node (ref "K9") (pin "2") (pinfunction "-_2") (pintype "passive"))
      (node (ref "Q9") (pin "3") (pinfunction "D_3") (pintype "passive"))
    )
    (net (code "105") (name "Net-(K10A-CA)") (class "Default")
      (node (ref "K10") (pin "3") (pinfunction "CA_3") (pintype "passive"))
      (node (ref "X3") (pin "10") (pinfunction "10_10") (pintype "passive"))
    )
    (net (code "106") (name "Net-(K10A-CB)") (class "Default")
      (node (ref "K10") (pin "4") (pinfunction "CB_4") (pintype "passive"))
      (node (ref "X2") (pin "10") (pinfunction "10_10") (pintype "passive"))
    )
    (net (code "107") (name "Net-(K10B--)") (class "Default")
      (node (ref "K10") (pin "2") (pinfunction "-_2") (pintype "passive"))
      (node (ref "Q10") (pin "3") (pinfunction "D_3") (pintype "passive"))
    )
    (net (code "108") (name "Net-(K11A-CA)") (class "Default")
      (node (ref "K11") (pin "3") (pinfunction "CA_3") (pintype "passive"))
      (node (ref "X3") (pin "11") (pinfunction "11_11") (pintype "passive"))
    )
    (net (code "109") (name "Net-(K11A-CB)") (class "Default")
      (node (ref "K11") (pin "4") (pinfunction "CB_4") (pintype "passive"))
      (node (ref "X2") (pin "11") (pinfunction "11_11") (pintype "passive"))
    )
    (net (code "110") (name "Net-(K11B--)") (class "Default")
      (node (ref "K11") (pin "2") (pinfunction "-_2") (pintype "passive"))
      (node (ref "Q11") (pin "3") (pinfunction "D_3") (pintype "passive"))
    )
    (net (code "111") (name "Net-(K12A-CA)") (class "Default")
      (node (ref "K12") (pin "3") (pinfunction "CA_3") (pintype "passive"))
      (node (ref "X3") (pin "12") (pinfunction "12_12") (pintype "passive"))
    )
    (net (code "112") (name "Net-(K12A-CB)") (class "Default")
      (node (ref "K12") (pin "4") (pinfunction "CB_4") (pintype "passive"))
      (node (ref "X2") (pin "12") (pinfunction "12_12") (pintype "passive"))
    )
    (net (code "113") (name "Net-(K12B--)") (class "Default")
      (node (ref "K12") (pin "2") (pinfunction "-_2") (pintype "passive"))
      (node (ref "Q12") (pin "3") (pinfunction "D_3") (pintype "passive"))
    )
    (net (code "114") (name "Net-(K13A-CA)") (class "Default")
      (node (ref "K13") (pin "3") (pinfunction "CA_3") (pintype "passive"))
      (node (ref "X3") (pin "13") (pinfunction "13_13") (pintype "passive"))
    )
    (net (code "115") (name "Net-(K13A-CB)") (class "Default")
      (node (ref "K13") (pin "4") (pinfunction "CB_4") (pintype "passive"))
      (node (ref "X2") (pin "13") (pinfunction "13_13") (pintype "passive"))
    )
    (net (code "116") (name "Net-(K13B--)") (class "Default")
      (node (ref "K13") (pin "2") (pinfunction "-_2") (pintype "passive"))
      (node (ref "Q13") (pin "3") (pinfunction "D_3") (pintype "passive"))
    )
    (net (code "117") (name "Net-(K14A-CA)") (class "Default")
      (node (ref "K14") (pin "3") (pinfunction "CA_3") (pintype "passive"))
      (node (ref "X3") (pin "14") (pinfunction "14_14") (pintype "passive"))
    )
    (net (code "118") (name "Net-(K14A-CB)") (class "Default")
      (node (ref "K14") (pin "4") (pinfunction "CB_4") (pintype "passive"))
      (node (ref "X2") (pin "14") (pinfunction "14_14") (pintype "passive"))
    )
    (net (code "119") (name "Net-(K14B--)") (class "Default")
      (node (ref "K14") (pin "2") (pinfunction "-_2") (pintype "passive"))
      (node (ref "Q14") (pin "3") (pinfunction "D_3") (pintype "passive"))
    )
    (net (code "120") (name "Net-(K15A-CA)") (class "Default")
      (node (ref "K15") (pin "3") (pinfunction "CA_3") (pintype "passive"))
      (node (ref "X3") (pin "15") (pinfunction "15_15") (pintype "passive"))
    )
    (net (code "121") (name "Net-(K15A-CB)") (class "Default")
      (node (ref "K15") (pin "4") (pinfunction "CB_4") (pintype "passive"))
      (node (ref "X2") (pin "15") (pinfunction "15_15") (pintype "passive"))
    )
    (net (code "122") (name "Net-(K15B--)") (class "Default")
      (node (ref "K15") (pin "2") (pinfunction "-_2") (pintype "passive"))
      (node (ref "Q15") (pin "3") (pinfunction "D_3") (pintype "passive"))
    )
    (net (code "123") (name "Net-(K16A-CA)") (class "Default")
      (node (ref "K16") (pin "3") (pinfunction "CA_3") (pintype "passive"))
      (node (ref "X3") (pin "16") (pinfunction "16_16") (pintype "passive"))
    )
    (net (code "124") (name "Net-(K16A-CB)") (class "Default")
      (node (ref "K16") (pin "4") (pinfunction "CB_4") (pintype "passive"))
      (node (ref "X2") (pin "16") (pinfunction "16_16") (pintype "passive"))
    )
    (net (code "125") (name "Net-(K16B--)") (class "Default")
      (node (ref "K16") (pin "2") (pinfunction "-_2") (pintype "passive"))
      (node (ref "Q16") (pin "3") (pinfunction "D_3") (pintype "passive"))
    )
    (net (code "126") (name "Net-(K17A-CA)") (class "Default")
      (node (ref "K17") (pin "3") (pinfunction "CA_3") (pintype "passive"))
      (node (ref "X3") (pin "17") (pinfunction "17_17") (pintype "passive"))
    )
    (net (code "127") (name "Net-(K17A-CB)") (class "Default")
      (node (ref "K17") (pin "4") (pinfunction "CB_4") (pintype "passive"))
      (node (ref "X2") (pin "17") (pinfunction "17_17") (pintype "passive"))
    )
    (net (code "128") (name "Net-(K17B--)") (class "Default")
      (node (ref "K17") (pin "2") (pinfunction "-_2") (pintype "passive"))
      (node (ref "Q17") (pin "3") (pinfunction "D_3") (pintype "passive"))
    )
    (net (code "129") (name "Net-(K18A-CA)") (class "Default")
      (node (ref "K18") (pin "3") (pinfunction "CA_3") (pintype "passive"))
      (node (ref "X3") (pin "18") (pinfunction "18_18") (pintype "passive"))
    )
    (net (code "130") (name "Net-(K18A-CB)") (class "Default")
      (node (ref "K18") (pin "4") (pinfunction "CB_4") (pintype "passive"))
      (node (ref "X2") (pin "18") (pinfunction "18_18") (pintype "passive"))
    )
    (net (code "131") (name "Net-(K18B--)") (class "Default")
      (node (ref "K18") (pin "2") (pinfunction "-_2") (pintype "passive"))
      (node (ref "Q18") (pin "3") (pinfunction "D_3") (pintype "passive"))
    )
    (net (code "132") (name "Net-(K19A-CA)") (class "Default")
      (node (ref "K19") (pin "3") (pinfunction "CA_3") (pintype "passive"))
      (node (ref "X3") (pin "19") (pinfunction "19_19") (pintype "passive"))
    )
    (net (code "133") (name "Net-(K19A-CB)") (class "Default")
      (node (ref "K19") (pin "4") (pinfunction "CB_4") (pintype "passive"))
      (node (ref "X2") (pin "19") (pinfunction "19_19") (pintype "passive"))
    )
    (net (code "134") (name "Net-(K19B--)") (class "Default")
      (node (ref "K19") (pin "2") (pinfunction "-_2") (pintype "passive"))
      (node (ref "Q19") (pin "3") (pinfunction "D_3") (pintype "passive"))
    )
    (net (code "135") (name "Net-(K20A-CA)") (class "Default")
      (node (ref "K20") (pin "3") (pinfunction "CA_3") (pintype "passive"))
      (node (ref "X3") (pin "20") (pinfunction "20_20") (pintype "passive"))
    )
    (net (code "136") (name "Net-(K20A-CB)") (class "Default")
      (node (ref "K20") (pin "4") (pinfunction "CB_4") (pintype "passive"))
      (node (ref "X2") (pin "20") (pinfunction "20_20") (pintype "passive"))
    )
    (net (code "137") (name "Net-(K20B--)") (class "Default")
      (node (ref "K20") (pin "2") (pinfunction "-_2") (pintype "passive"))
      (node (ref "Q20") (pin "3") (pinfunction "D_3") (pintype "passive"))
    )
    (net (code "138") (name "Net-(K21A-CA)") (class "Default")
      (node (ref "K21") (pin "3") (pinfunction "CA_3") (pintype "passive"))
      (node (ref "X3") (pin "21") (pinfunction "21_21") (pintype "passive"))
    )
    (net (code "139") (name "Net-(K21A-CB)") (class "Default")
      (node (ref "K21") (pin "4") (pinfunction "CB_4") (pintype "passive"))
      (node (ref "X2") (pin "21") (pinfunction "21_21") (pintype "passive"))
    )
    (net (code "140") (name "Net-(K21B--)") (class "Default")
      (node (ref "K21") (pin "2") (pinfunction "-_2") (pintype "passive"))
      (node (ref "Q21") (pin "3") (pinfunction "D_3") (pintype "passive"))
    )
    (net (code "141") (name "Net-(K22A-CA)") (class "Default")
      (node (ref "K22") (pin "3") (pinfunction "CA_3") (pintype "passive"))
      (node (ref "X3") (pin "22") (pinfunction "22_22") (pintype "passive"))
    )
    (net (code "142") (name "Net-(K22A-CB)") (class "Default")
      (node (ref "K22") (pin "4") (pinfunction "CB_4") (pintype "passive"))
      (node (ref "X2") (pin "22") (pinfunction "22_22") (pintype "passive"))
    )
    (net (code "143") (name "Net-(K22B--)") (class "Default")
      (node (ref "K22") (pin "2") (pinfunction "-_2") (pintype "passive"))
      (node (ref "Q22") (pin "3") (pinfunction "D_3") (pintype "passive"))
    )
    (net (code "144") (name "Net-(K23A-CA)") (class "Default")
      (node (ref "K23") (pin "3") (pinfunction "CA_3") (pintype "passive"))
      (node (ref "X3") (pin "23") (pinfunction "23_23") (pintype "passive"))
    )
    (net (code "145") (name "Net-(K23A-CB)") (class "Default")
      (node (ref "K23") (pin "4") (pinfunction "CB_4") (pintype "passive"))
      (node (ref "X2") (pin "23") (pinfunction "23_23") (pintype "passive"))
    )
    (net (code "146") (name "Net-(K23B--)") (class "Default")
      (node (ref "K23") (pin "2") (pinfunction "-_2") (pintype "passive"))
      (node (ref "Q23") (pin "3") (pinfunction "D_3") (pintype "passive"))
    )
    (net (code "147") (name "Net-(K24A-CA)") (class "Default")
      (node (ref "K24") (pin "3") (pinfunction "CA_3") (pintype "passive"))
      (node (ref "X3") (pin "24") (pinfunction "24_24") (pintype "passive"))
    )
    (net (code "148") (name "Net-(K24A-CB)") (class "Default")
      (node (ref "K24") (pin "4") (pinfunction "CB_4") (pintype "passive"))
      (node (ref "X2") (pin "24") (pinfunction "24_24") (pintype "passive"))
    )
    (net (code "149") (name "Net-(K24B--)") (class "Default")
      (node (ref "K24") (pin "2") (pinfunction "-_2") (pintype "passive"))
      (node (ref "Q24") (pin "3") (pinfunction "D_3") (pintype "passive"))
    )
    (net (code "150") (name "Net-(K25A-CA)") (class "Default")
      (node (ref "K25") (pin "3") (pinfunction "CA_3") (pintype "passive"))
      (node (ref "X3") (pin "25") (pinfunction "25_25") (pintype "passive"))
    )
    (net (code "151") (name "Net-(K25A-CB)") (class "Default")
      (node (ref "K25") (pin "4") (pinfunction "CB_4") (pintype "passive"))
      (node (ref "X2") (pin "25") (pinfunction "25_25") (pintype "passive"))
    )
    (net (code "152") (name "Net-(K25B--)") (class "Default")
      (node (ref "K25") (pin "2") (pinfunction "-_2") (pintype "passive"))
      (node (ref "Q25") (pin "3") (pinfunction "D_3") (pintype "passive"))
    )
    (net (code "153") (name "Net-(K26A-CA)") (class "Default")
      (node (ref "K26") (pin "3") (pinfunction "CA_3") (pintype "passive"))
      (node (ref "X3") (pin "26") (pinfunction "26_26") (pintype "passive"))
    )
    (net (code "154") (name "Net-(K26A-CB)") (class "Default")
      (node (ref "K26") (pin "4") (pinfunction "CB_4") (pintype "passive"))
      (node (ref "X2") (pin "26") (pinfunction "26_26") (pintype "passive"))
    )
    (net (code "155") (name "Net-(K26B--)") (class "Default")
      (node (ref "K26") (pin "2") (pinfunction "-_2") (pintype "passive"))
      (node (ref "Q26") (pin "3") (pinfunction "D_3") (pintype "passive"))
    )
    (net (code "156") (name "Net-(K27A-CA)") (class "Default")
      (node (ref "K27") (pin "3") (pinfunction "CA_3") (pintype "passive"))
      (node (ref "X3") (pin "27") (pinfunction "27_27") (pintype "passive"))
    )
    (net (code "157") (name "Net-(K27A-CB)") (class "Default")
      (node (ref "K27") (pin "4") (pinfunction "CB_4") (pintype "passive"))
      (node (ref "X2") (pin "27") (pinfunction "27_27") (pintype "passive"))
    )
    (net (code "158") (name "Net-(K27B--)") (class "Default")
      (node (ref "K27") (pin "2") (pinfunction "-_2") (pintype "passive"))
      (node (ref "Q27") (pin "3") (pinfunction "D_3") (pintype "passive"))
    )
    (net (code "159") (name "Net-(K28A-CA)") (class "Default")
      (node (ref "K28") (pin "3") (pinfunction "CA_3") (pintype "passive"))
      (node (ref "X3") (pin "28") (pinfunction "28_28") (pintype "passive"))
    )
    (net (code "160") (name "Net-(K28A-CB)") (class "Default")
      (node (ref "K28") (pin "4") (pinfunction "CB_4") (pintype "passive"))
      (node (ref "X2") (pin "28") (pinfunction "28_28") (pintype "passive"))
    )
    (net (code "161") (name "Net-(K28B--)") (class "Default")
      (node (ref "K28") (pin "2") (pinfunction "-_2") (pintype "passive"))
      (node (ref "Q28") (pin "3") (pinfunction "D_3") (pintype "passive"))
    )
    (net (code "162") (name "Net-(K29A-CA)") (class "Default")
      (node (ref "K29") (pin "3") (pinfunction "CA_3") (pintype "passive"))
      (node (ref "X3") (pin "29") (pinfunction "29_29") (pintype "passive"))
    )
    (net (code "163") (name "Net-(K29A-CB)") (class "Default")
      (node (ref "K29") (pin "4") (pinfunction "CB_4") (pintype "passive"))
      (node (ref "X2") (pin "29") (pinfunction "29_29") (pintype "passive"))
    )
    (net (code "164") (name "Net-(K29B--)") (class "Default")
      (node (ref "K29") (pin "2") (pinfunction "-_2") (pintype "passive"))
      (node (ref "Q29") (pin "3") (pinfunction "D_3") (pintype "passive"))
    )
    (net (code "165") (name "Net-(K30A-CA)") (class "Default")
      (node (ref "K30") (pin "3") (pinfunction "CA_3") (pintype "passive"))
      (node (ref "X3") (pin "30") (pinfunction "30_30") (pintype "passive"))
    )
    (net (code "166") (name "Net-(K30A-CB)") (class "Default")
      (node (ref "K30") (pin "4") (pinfunction "CB_4") (pintype "passive"))
      (node (ref "X2") (pin "30") (pinfunction "30_30") (pintype "passive"))
    )
    (net (code "167") (name "Net-(K30B--)") (class "Default")
      (node (ref "K30") (pin "2") (pinfunction "-_2") (pintype "passive"))
      (node (ref "Q30") (pin "3") (pinfunction "D_3") (pintype "passive"))
    )
    (net (code "168") (name "Net-(K31A-CA)") (class "Default")
      (node (ref "K31") (pin "3") (pinfunction "CA_3") (pintype "passive"))
      (node (ref "X3") (pin "31") (pinfunction "31_31") (pintype "passive"))
    )
    (net (code "169") (name "Net-(K31A-CB)") (class "Default")
      (node (ref "K31") (pin "4") (pinfunction "CB_4") (pintype "passive"))
      (node (ref "X2") (pin "31") (pinfunction "31_31") (pintype "passive"))
    )
    (net (code "170") (name "Net-(K31B--)") (class "Default")
      (node (ref "K31") (pin "2") (pinfunction "-_2") (pintype "passive"))
      (node (ref "Q31") (pin "3") (pinfunction "D_3") (pintype "passive"))
    )
    (net (code "171") (name "Net-(K32A-CA)") (class "Default")
      (node (ref "K32") (pin "3") (pinfunction "CA_3") (pintype "passive"))
      (node (ref "X3") (pin "32") (pinfunction "32_32") (pintype "passive"))
    )
    (net (code "172") (name "Net-(K32A-CB)") (class "Default")
      (node (ref "K32") (pin "4") (pinfunction "CB_4") (pintype "passive"))
      (node (ref "X2") (pin "32") (pinfunction "32_32") (pintype "passive"))
    )
    (net (code "173") (name "Net-(K32B--)") (class "Default")
      (node (ref "K32") (pin "2") (pinfunction "-_2") (pintype "passive"))
      (node (ref "Q32") (pin "3") (pinfunction "D_3") (pintype "passive"))
    )
    (net (code "174") (name "Net-(K33A-CA)") (class "Default")
      (node (ref "K33") (pin "3") (pinfunction "CA_3") (pintype "passive"))
      (node (ref "X3") (pin "33") (pinfunction "33_33") (pintype "passive"))
    )
    (net (code "175") (name "Net-(K33A-CB)") (class "Default")
      (node (ref "K33") (pin "4") (pinfunction "CB_4") (pintype "passive"))
      (node (ref "X2") (pin "33") (pinfunction "33_33") (pintype "passive"))
    )
    (net (code "176") (name "Net-(K33B--)") (class "Default")
      (node (ref "K33") (pin "2") (pinfunction "-_2") (pintype "passive"))
      (node (ref "Q33") (pin "3") (pinfunction "D_3") (pintype "passive"))
    )
    (net (code "177") (name "Net-(K34A-CA)") (class "Default")
      (node (ref "K34") (pin "3") (pinfunction "CA_3") (pintype "passive"))
      (node (ref "X3") (pin "34") (pinfunction "34_34") (pintype "passive"))
    )
    (net (code "178") (name "Net-(K34A-CB)") (class "Default")
      (node (ref "K34") (pin "4") (pinfunction "CB_4") (pintype "passive"))
      (node (ref "X2") (pin "34") (pinfunction "34_34") (pintype "passive"))
    )
    (net (code "179") (name "Net-(K34B--)") (class "Default")
      (node (ref "K34") (pin "2") (pinfunction "-_2") (pintype "passive"))
      (node (ref "Q34") (pin "3") (pinfunction "D_3") (pintype "passive"))
    )
    (net (code "180") (name "Net-(K35A-CA)") (class "Default")
      (node (ref "K35") (pin "3") (pinfunction "CA_3") (pintype "passive"))
      (node (ref "X3") (pin "35") (pinfunction "35_35") (pintype "passive"))
    )
    (net (code "181") (name "Net-(K35A-CB)") (class "Default")
      (node (ref "K35") (pin "4") (pinfunction "CB_4") (pintype "passive"))
      (node (ref "X2") (pin "35") (pinfunction "35_35") (pintype "passive"))
    )
    (net (code "182") (name "Net-(K35B--)") (class "Default")
      (node (ref "K35") (pin "2") (pinfunction "-_2") (pintype "passive"))
      (node (ref "Q35") (pin "3") (pinfunction "D_3") (pintype "passive"))
    )
    (net (code "183") (name "Net-(K36A-CA)") (class "Default")
      (node (ref "K36") (pin "3") (pinfunction "CA_3") (pintype "passive"))
      (node (ref "X3") (pin "36") (pinfunction "36_36") (pintype "passive"))
    )
    (net (code "184") (name "Net-(K36A-CB)") (class "Default")
      (node (ref "K36") (pin "4") (pinfunction "CB_4") (pintype "passive"))
      (node (ref "X2") (pin "36") (pinfunction "36_36") (pintype "passive"))
    )
    (net (code "185") (name "Net-(K36B--)") (class "Default")
      (node (ref "K36") (pin "2") (pinfunction "-_2") (pintype "passive"))
      (node (ref "Q36") (pin "3") (pinfunction "D_3") (pintype "passive"))
    )
    (net (code "186") (name "Net-(K37A-CA)") (class "Default")
      (node (ref "K37") (pin "3") (pinfunction "CA_3") (pintype "passive"))
      (node (ref "X3") (pin "37") (pinfunction "37_37") (pintype "passive"))
    )
    (net (code "187") (name "Net-(K37A-CB)") (class "Default")
      (node (ref "K37") (pin "4") (pinfunction "CB_4") (pintype "passive"))
      (node (ref "X2") (pin "37") (pinfunction "37_37") (pintype "passive"))
    )
    (net (code "188") (name "Net-(K37B--)") (class "Default")
      (node (ref "K37") (pin "2") (pinfunction "-_2") (pintype "passive"))
      (node (ref "Q37") (pin "3") (pinfunction "D_3") (pintype "passive"))
    )
    (net (code "189") (name "Net-(K38A-CA)") (class "Default")
      (node (ref "K38") (pin "3") (pinfunction "CA_3") (pintype "passive"))
      (node (ref "X3") (pin "38") (pinfunction "38_38") (pintype "passive"))
    )
    (net (code "190") (name "Net-(K38A-CB)") (class "Default")
      (node (ref "K38") (pin "4") (pinfunction "CB_4") (pintype "passive"))
      (node (ref "X2") (pin "38") (pinfunction "38_38") (pintype "passive"))
    )
    (net (code "191") (name "Net-(K38B--)") (class "Default")
      (node (ref "K38") (pin "2") (pinfunction "-_2") (pintype "passive"))
      (node (ref "Q38") (pin "3") (pinfunction "D_3") (pintype "passive"))
    )
    (net (code "192") (name "Net-(K39A-CA)") (class "Default")
      (node (ref "K39") (pin "3") (pinfunction "CA_3") (pintype "passive"))
      (node (ref "X3") (pin "39") (pinfunction "39_39") (pintype "passive"))
    )
    (net (code "193") (name "Net-(K39A-CB)") (class "Default")
      (node (ref "K39") (pin "4") (pinfunction "CB_4") (pintype "passive"))
      (node (ref "X2") (pin "39") (pinfunction "39_39") (pintype "passive"))
    )
    (net (code "194") (name "Net-(K39B--)") (class "Default")
      (node (ref "K39") (pin "2") (pinfunction "-_2") (pintype "passive"))
      (node (ref "Q39") (pin "3") (pinfunction "D_3") (pintype "passive"))
    )
    (net (code "195") (name "Net-(K40A-CA)") (class "Default")
      (node (ref "K40") (pin "3") (pinfunction "CA_3") (pintype "passive"))
      (node (ref "X3") (pin "40") (pinfunction "40_40") (pintype "passive"))
    )
    (net (code "196") (name "Net-(K40A-CB)") (class "Default")
      (node (ref "K40") (pin "4") (pinfunction "CB_4") (pintype "passive"))
      (node (ref "X2") (pin "40") (pinfunction "40_40") (pintype "passive"))
    )
    (net (code "197") (name "Net-(K40B--)") (class "Default")
      (node (ref "K40") (pin "2") (pinfunction "-_2") (pintype "passive"))
      (node (ref "Q40") (pin "3") (pinfunction "D_3") (pintype "passive"))
    )
    (net (code "198") (name "Net-(K41A-CA)") (class "Default")
      (node (ref "K41") (pin "3") (pinfunction "CA_3") (pintype "passive"))
      (node (ref "X3") (pin "41") (pinfunction "41_41") (pintype "passive"))
    )
    (net (code "199") (name "Net-(K41A-CB)") (class "Default")
      (node (ref "K41") (pin "4") (pinfunction "CB_4") (pintype "passive"))
      (node (ref "X2") (pin "41") (pinfunction "41_41") (pintype "passive"))
    )
    (net (code "200") (name "Net-(K41B--)") (class "Default")
      (node (ref "K41") (pin "2") (pinfunction "-_2") (pintype "passive"))
      (node (ref "Q41") (pin "3") (pinfunction "D_3") (pintype "passive"))
    )
    (net (code "201") (name "Net-(K42A-CA)") (class "Default")
      (node (ref "K42") (pin "3") (pinfunction "CA_3") (pintype "passive"))
      (node (ref "X3") (pin "42") (pinfunction "42_42") (pintype "passive"))
    )
    (net (code "202") (name "Net-(K42A-CB)") (class "Default")
      (node (ref "K42") (pin "4") (pinfunction "CB_4") (pintype "passive"))
      (node (ref "X2") (pin "42") (pinfunction "42_42") (pintype "passive"))
    )
    (net (code "203") (name "Net-(K42B--)") (class "Default")
      (node (ref "K42") (pin "2") (pinfunction "-_2") (pintype "passive"))
      (node (ref "Q42") (pin "3") (pinfunction "D_3") (pintype "passive"))
    )
    (net (code "204") (name "Net-(K43A-CA)") (class "Default")
      (node (ref "K43") (pin "3") (pinfunction "CA_3") (pintype "passive"))
      (node (ref "X3") (pin "43") (pinfunction "43_43") (pintype "passive"))
    )
    (net (code "205") (name "Net-(K43A-CB)") (class "Default")
      (node (ref "K43") (pin "4") (pinfunction "CB_4") (pintype "passive"))
      (node (ref "X2") (pin "43") (pinfunction "43_43") (pintype "passive"))
    )
    (net (code "206") (name "Net-(K43B--)") (class "Default")
      (node (ref "K43") (pin "2") (pinfunction "-_2") (pintype "passive"))
      (node (ref "Q43") (pin "3") (pinfunction "D_3") (pintype "passive"))
    )
    (net (code "207") (name "Net-(K44A-CA)") (class "Default")
      (node (ref "K44") (pin "3") (pinfunction "CA_3") (pintype "passive"))
      (node (ref "X3") (pin "44") (pinfunction "44_44") (pintype "passive"))
    )
    (net (code "208") (name "Net-(K44A-CB)") (class "Default")
      (node (ref "K44") (pin "4") (pinfunction "CB_4") (pintype "passive"))
      (node (ref "X2") (pin "44") (pinfunction "44_44") (pintype "passive"))
    )
    (net (code "209") (name "Net-(K44B--)") (class "Default")
      (node (ref "K44") (pin "2") (pinfunction "-_2") (pintype "passive"))
      (node (ref "Q44") (pin "3") (pinfunction "D_3") (pintype "passive"))
    )
    (net (code "210") (name "Net-(K45A-CA)") (class "Default")
      (node (ref "K45") (pin "3") (pinfunction "CA_3") (pintype "passive"))
      (node (ref "X3") (pin "45") (pinfunction "45_45") (pintype "passive"))
    )
    (net (code "211") (name "Net-(K45A-CB)") (class "Default")
      (node (ref "K45") (pin "4") (pinfunction "CB_4") (pintype "passive"))
      (node (ref "X2") (pin "45") (pinfunction "45_45") (pintype "passive"))
    )
    (net (code "212") (name "Net-(K45B--)") (class "Default")
      (node (ref "K45") (pin "2") (pinfunction "-_2") (pintype "passive"))
      (node (ref "Q45") (pin "3") (pinfunction "D_3") (pintype "passive"))
    )
    (net (code "213") (name "Net-(K46A-CA)") (class "Default")
      (node (ref "K46") (pin "3") (pinfunction "CA_3") (pintype "passive"))
      (node (ref "X3") (pin "46") (pinfunction "46_46") (pintype "passive"))
    )
    (net (code "214") (name "Net-(K46A-CB)") (class "Default")
      (node (ref "K46") (pin "4") (pinfunction "CB_4") (pintype "passive"))
      (node (ref "X2") (pin "46") (pinfunction "46_46") (pintype "passive"))
    )
    (net (code "215") (name "Net-(K46B--)") (class "Default")
      (node (ref "K46") (pin "2") (pinfunction "-_2") (pintype "passive"))
      (node (ref "Q46") (pin "3") (pinfunction "D_3") (pintype "passive"))
    )
    (net (code "216") (name "Net-(K47A-CA)") (class "Default")
      (node (ref "K47") (pin "3") (pinfunction "CA_3") (pintype "passive"))
      (node (ref "X3") (pin "47") (pinfunction "47_47") (pintype "passive"))
    )
    (net (code "217") (name "Net-(K47A-CB)") (class "Default")
      (node (ref "K47") (pin "4") (pinfunction "CB_4") (pintype "passive"))
      (node (ref "X2") (pin "47") (pinfunction "47_47") (pintype "passive"))
    )
    (net (code "218") (name "Net-(K47B--)") (class "Default")
      (node (ref "K47") (pin "2") (pinfunction "-_2") (pintype "passive"))
      (node (ref "Q47") (pin "3") (pinfunction "D_3") (pintype "passive"))
    )
    (net (code "219") (name "Net-(K48A-CA)") (class "Default")
      (node (ref "K48") (pin "3") (pinfunction "CA_3") (pintype "passive"))
      (node (ref "X3") (pin "48") (pinfunction "48_48") (pintype "passive"))
    )
    (net (code "220") (name "Net-(K48A-CB)") (class "Default")
      (node (ref "K48") (pin "4") (pinfunction "CB_4") (pintype "passive"))
      (node (ref "X2") (pin "48") (pinfunction "48_48") (pintype "passive"))
    )
    (net (code "221") (name "Net-(K48B--)") (class "Default")
      (node (ref "K48") (pin "2") (pinfunction "-_2") (pintype "passive"))
      (node (ref "Q48") (pin "3") (pinfunction "D_3") (pintype "passive"))
    )
  )
)
